# A-14732-40023.net
KiCad netlist of a schematic drawn in EAGLE
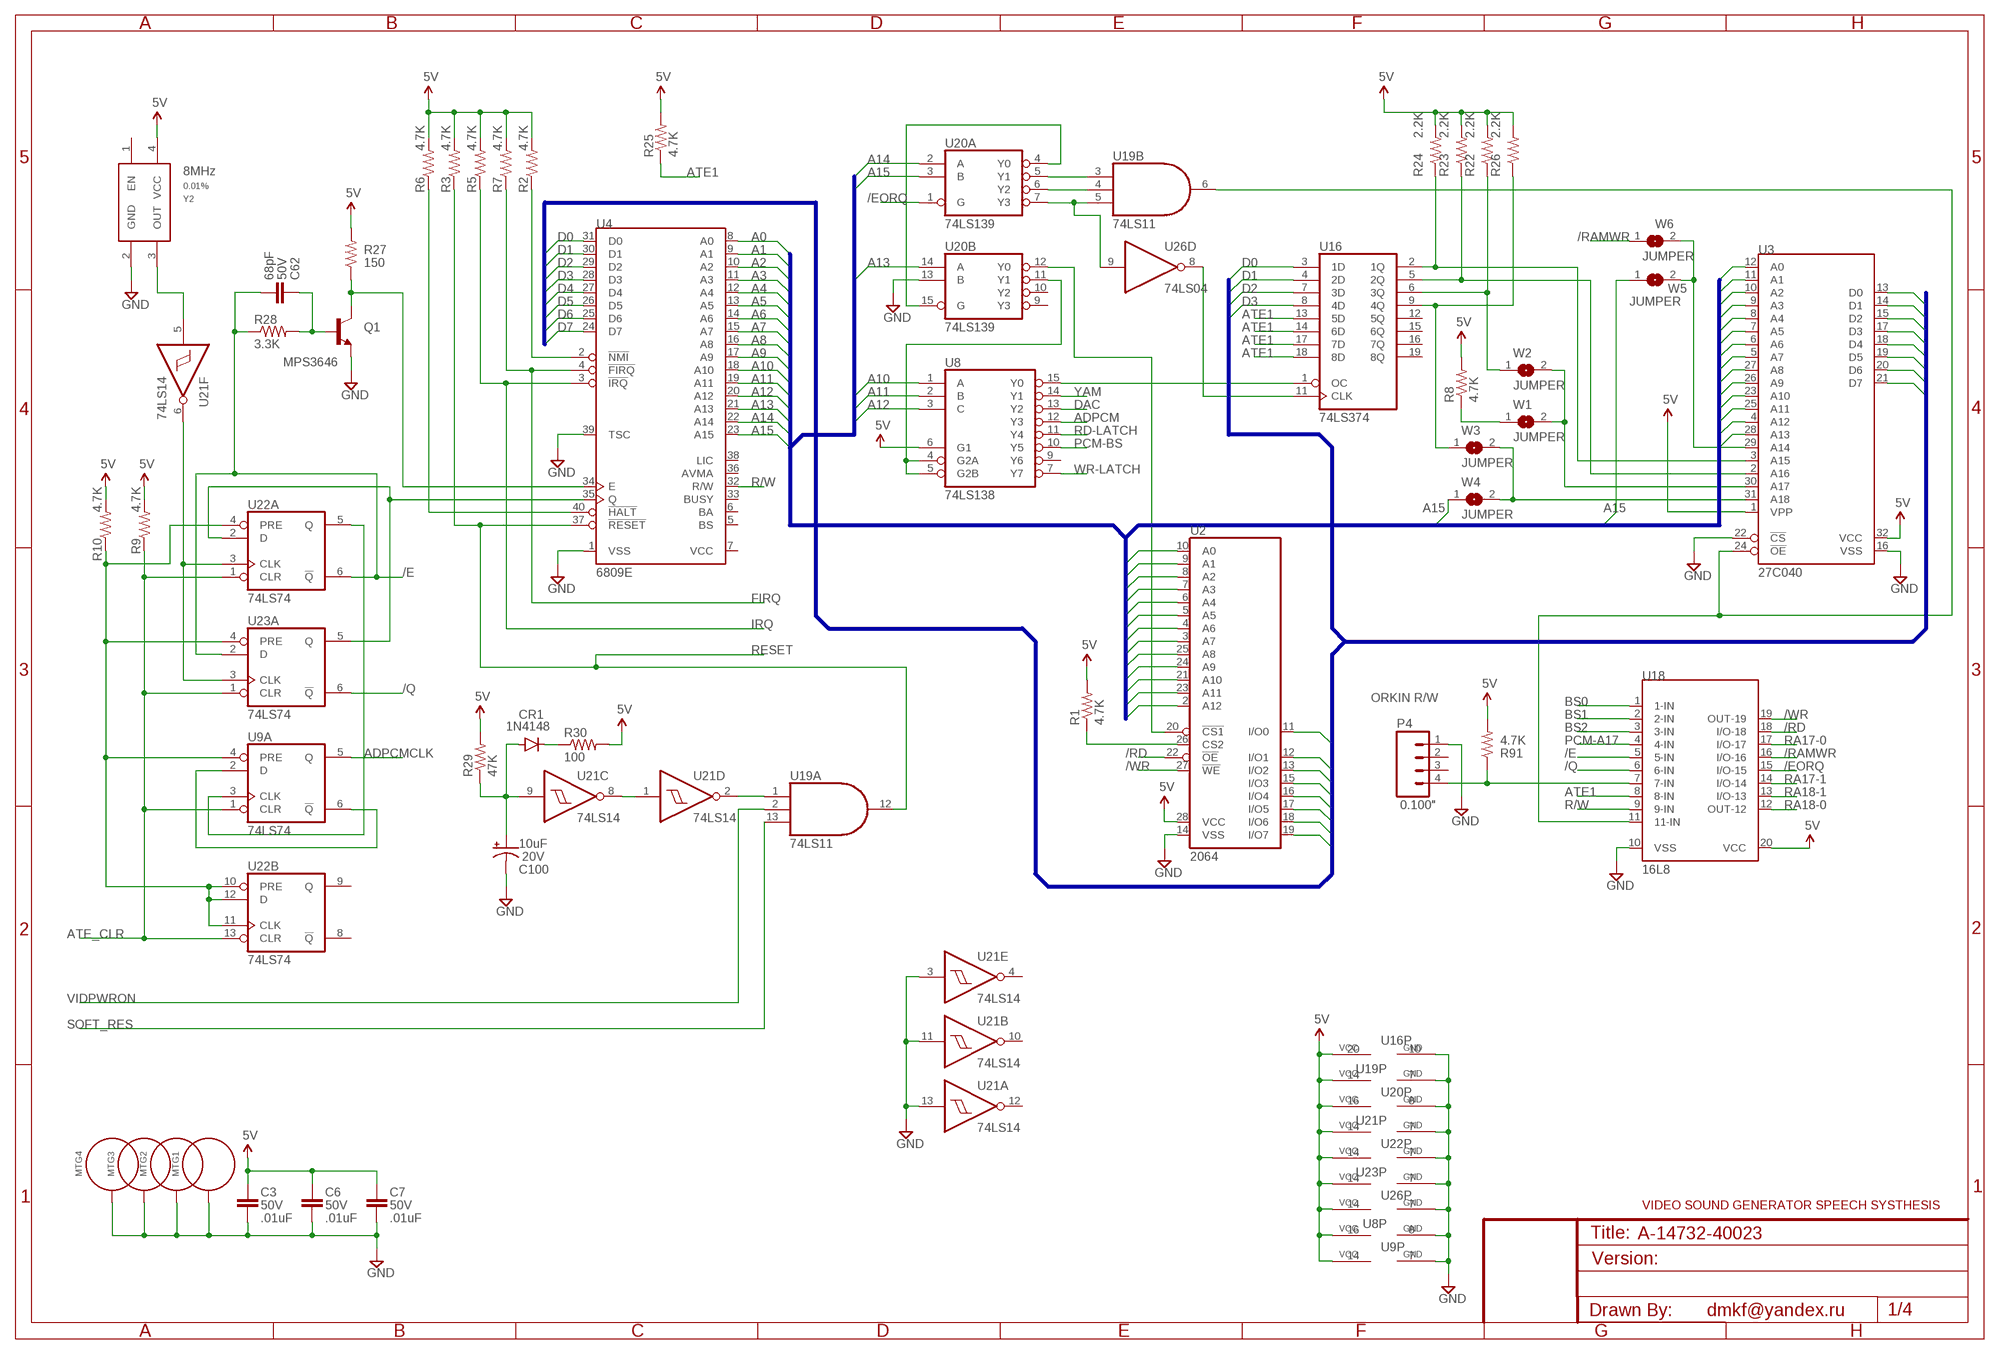
[diagram p0: schematic, sheet 1]
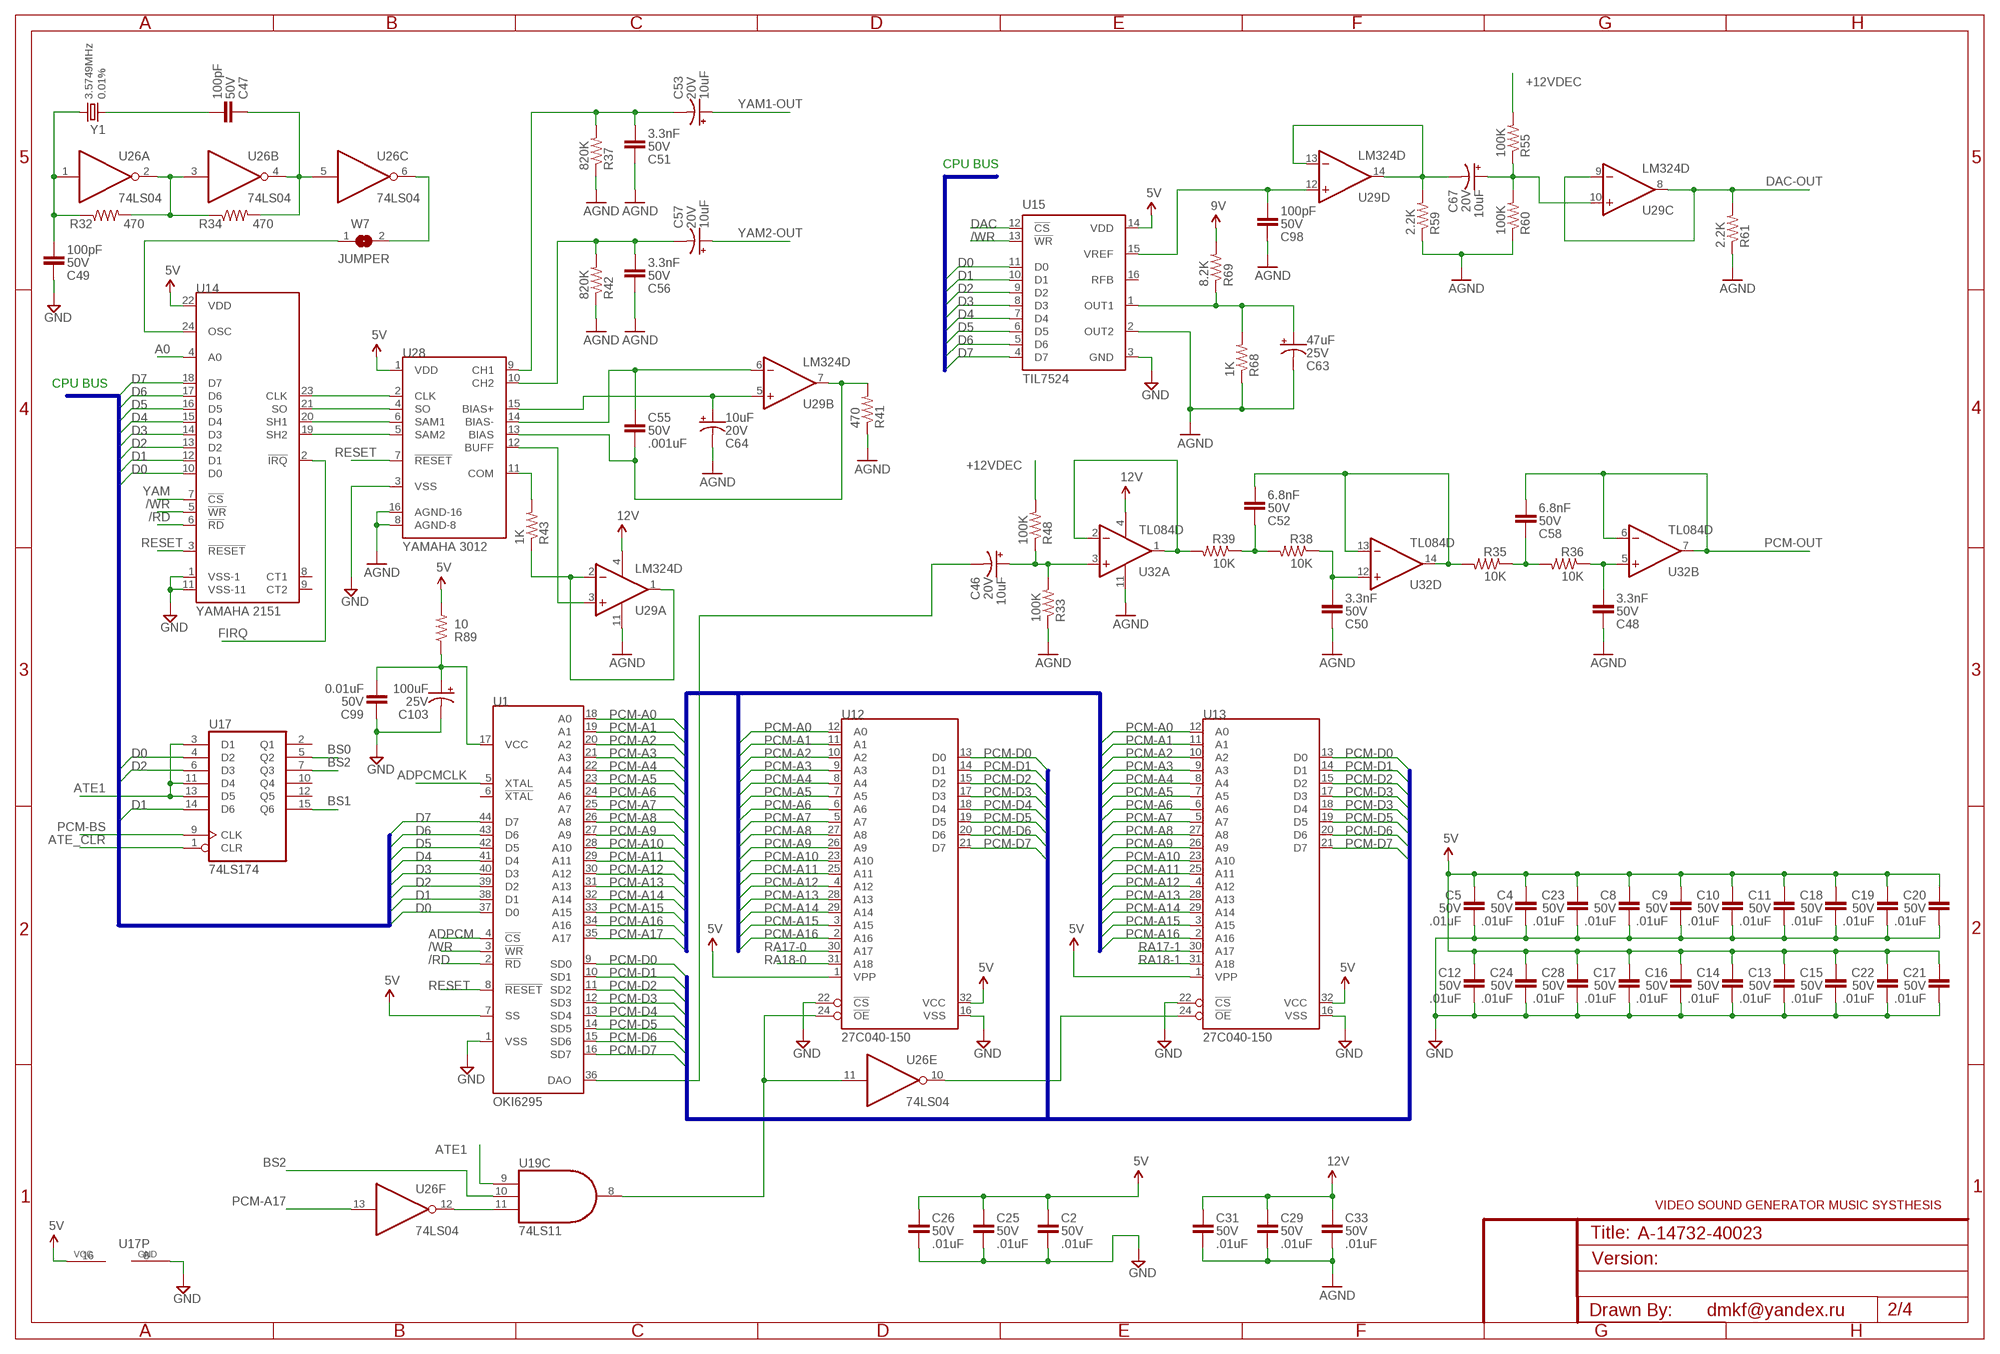
[diagram p1: schematic, sheet 2]
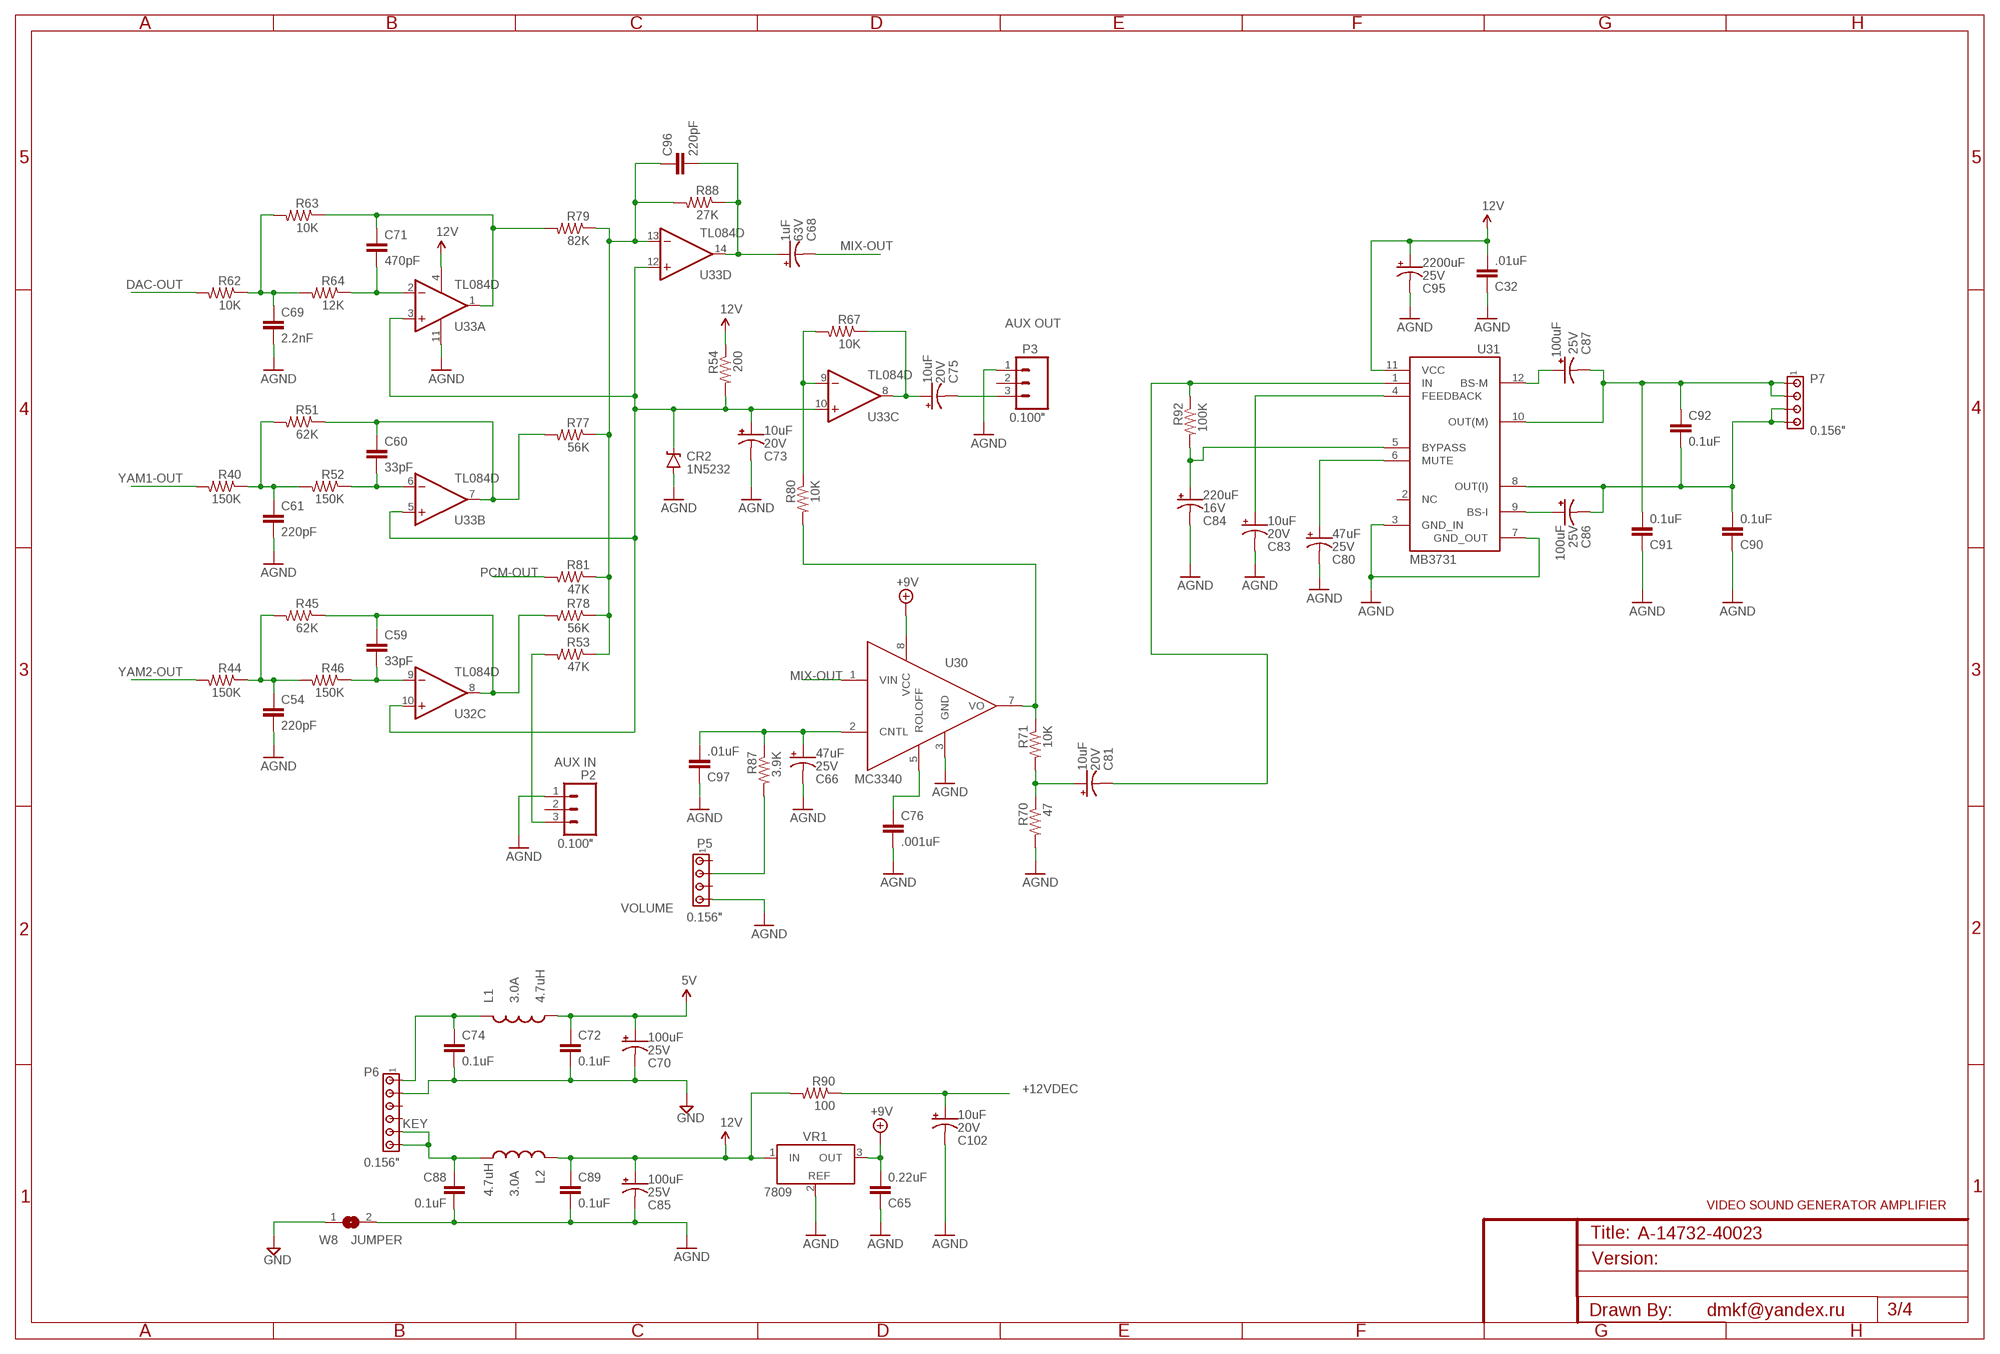
[diagram p2: schematic, sheet 3]
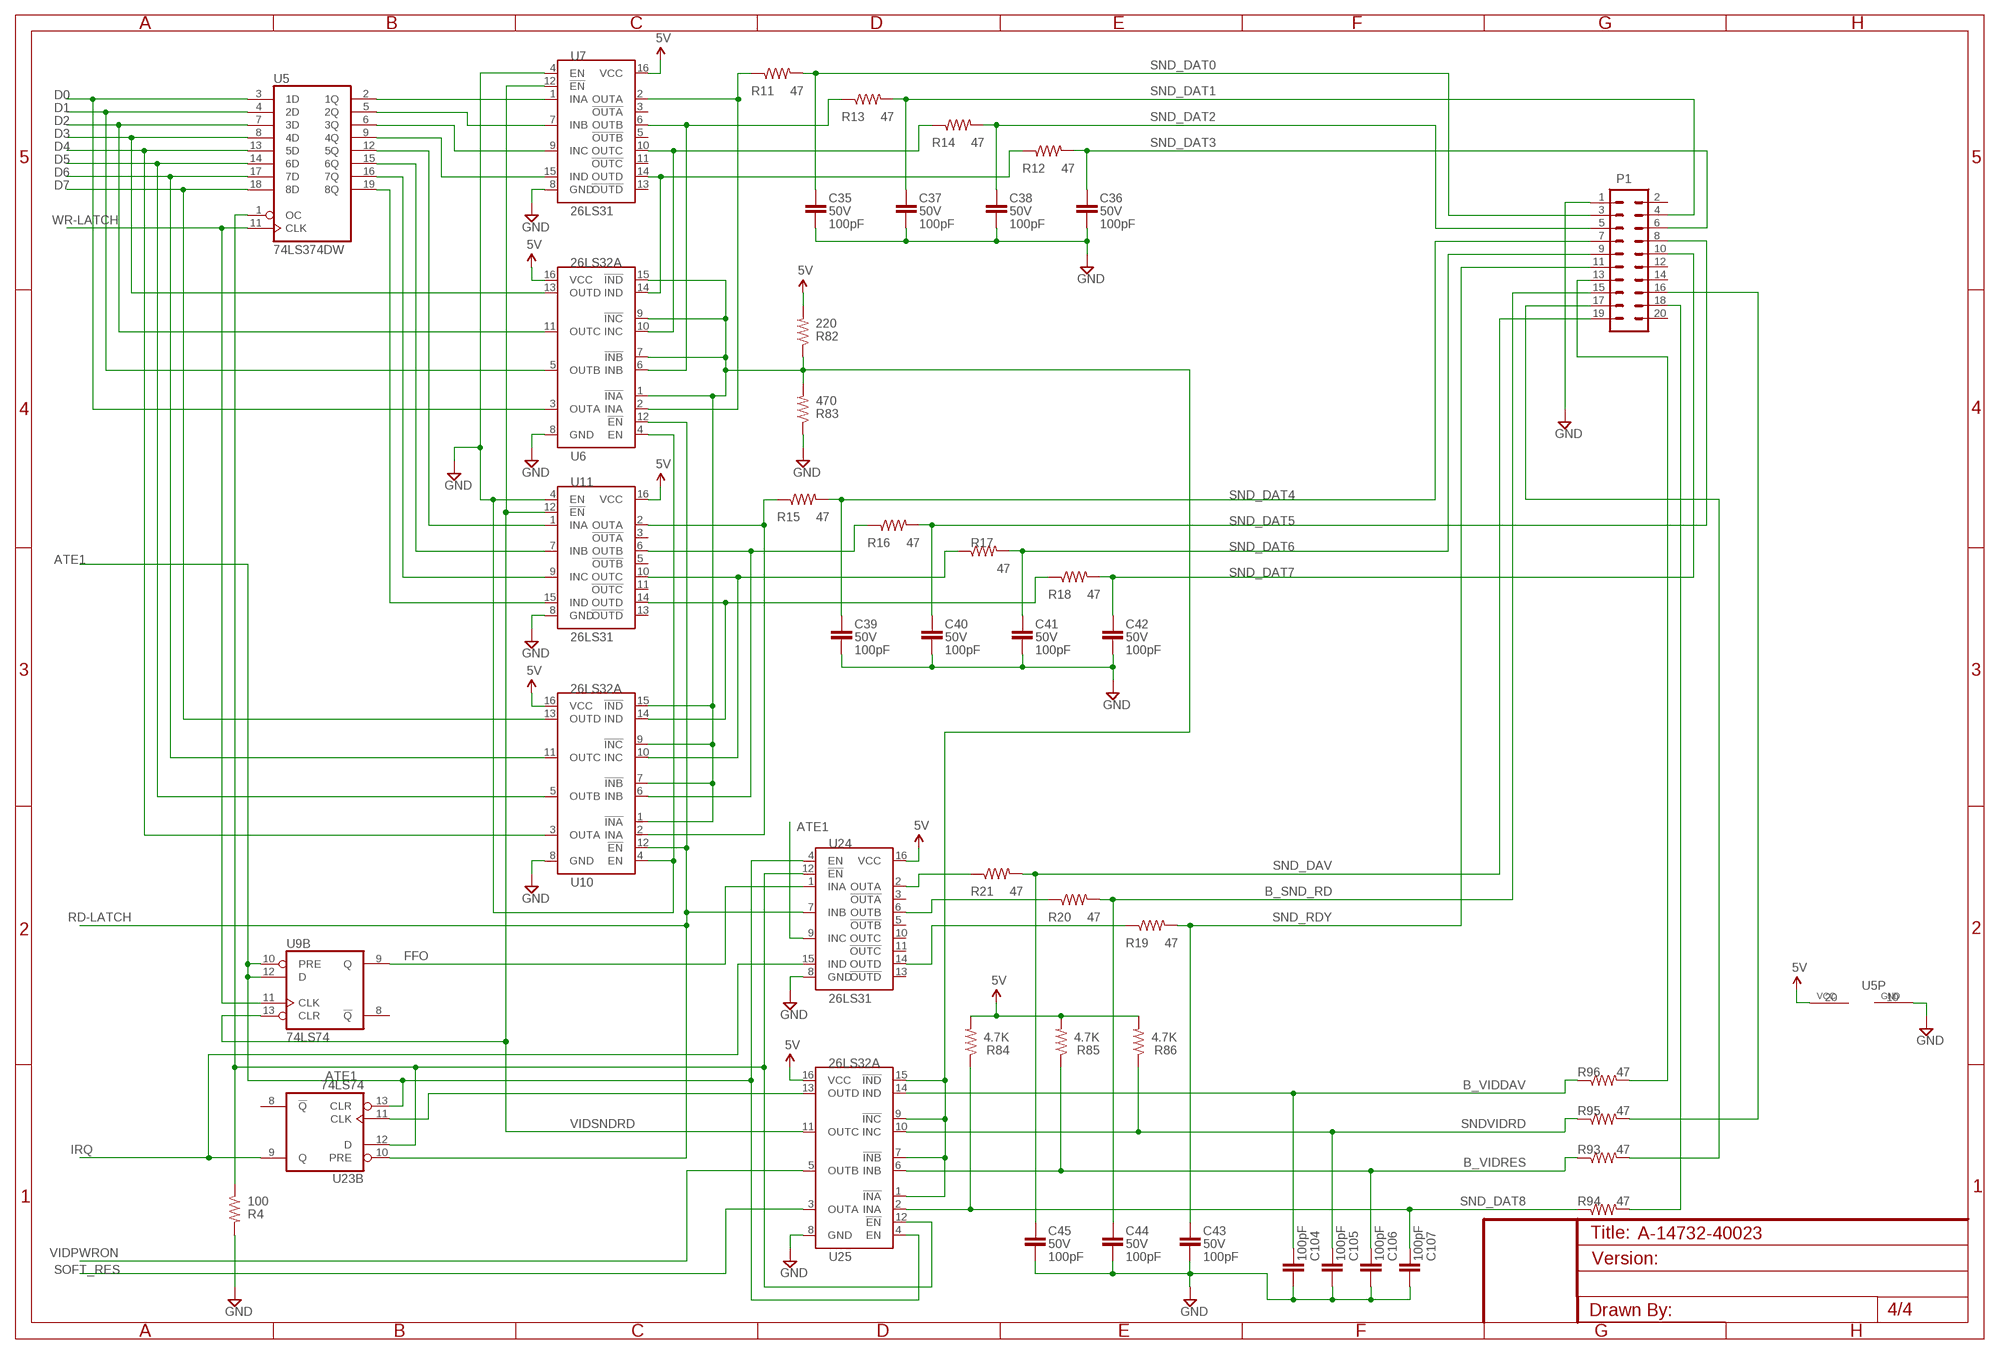
[diagram p3: schematic, sheet 4]

(export (version "E")
  (design (tool "Eeschema 10.0.6"))
  (components
    (comp (ref "C35")
      (value "100pF")
      (footprint "eagle-import:0805")
      (fields (field (name "VOLTAGE") "50V"))
      (libsource (lib "eagle-import") (part "CAP0805"))
    )
    (comp (ref "C36")
      (value "100pF")
      (footprint "eagle-import:0805")
      (fields (field (name "VOLTAGE") "50V"))
      (libsource (lib "eagle-import") (part "CAP0805"))
    )
    (comp (ref "C37")
      (value "100pF")
      (footprint "eagle-import:0805")
      (fields (field (name "VOLTAGE") "50V"))
      (libsource (lib "eagle-import") (part "CAP0805"))
    )
    (comp (ref "C38")
      (value "100pF")
      (footprint "eagle-import:0805")
      (fields (field (name "VOLTAGE") "50V"))
      (libsource (lib "eagle-import") (part "CAP0805"))
    )
    (comp (ref "C39")
      (value "100pF")
      (footprint "eagle-import:0805")
      (fields (field (name "VOLTAGE") "50V"))
      (libsource (lib "eagle-import") (part "CAP0805"))
    )
    (comp (ref "C40")
      (value "100pF")
      (footprint "eagle-import:0805")
      (fields (field (name "VOLTAGE") "50V"))
      (libsource (lib "eagle-import") (part "CAP0805"))
    )
    (comp (ref "C41")
      (value "100pF")
      (footprint "eagle-import:0805")
      (fields (field (name "VOLTAGE") "50V"))
      (libsource (lib "eagle-import") (part "CAP0805"))
    )
    (comp (ref "C42")
      (value "100pF")
      (footprint "eagle-import:0805")
      (fields (field (name "VOLTAGE") "50V"))
      (libsource (lib "eagle-import") (part "CAP0805"))
    )
    (comp (ref "C43")
      (value "100pF")
      (footprint "eagle-import:0805")
      (fields (field (name "VOLTAGE") "50V"))
      (libsource (lib "eagle-import") (part "CAP0805"))
    )
    (comp (ref "C44")
      (value "100pF")
      (footprint "eagle-import:0805")
      (fields (field (name "VOLTAGE") "50V"))
      (libsource (lib "eagle-import") (part "CAP0805"))
    )
    (comp (ref "C45")
      (value "100pF")
      (footprint "eagle-import:0805")
      (fields (field (name "VOLTAGE") "50V"))
      (libsource (lib "eagle-import") (part "CAP0805"))
    )
    (comp (ref "C104")
      (value "100pF")
      (footprint "eagle-import:0805")
      (fields (field (name "VOLTAGE") "50V"))
      (libsource (lib "eagle-import") (part "CAP0805"))
    )
    (comp (ref "C105")
      (value "100pF")
      (footprint "eagle-import:0805")
      (fields (field (name "VOLTAGE") "50V"))
      (libsource (lib "eagle-import") (part "CAP0805"))
    )
    (comp (ref "C106")
      (value "100pF")
      (footprint "eagle-import:0805")
      (fields (field (name "VOLTAGE") "50V"))
      (libsource (lib "eagle-import") (part "CAP0805"))
    )
    (comp (ref "C107")
      (value "100pF")
      (footprint "eagle-import:0805")
      (fields (field (name "VOLTAGE") "50V"))
      (libsource (lib "eagle-import") (part "CAP0805"))
    )
    (comp (ref "P1")
      (value "M10X2ROUND_NOSILK")
      (footprint "eagle-import:2X10_ROUND_NOSILK")
      (libsource (lib "eagle-import") (part "M10X2ROUND_NOSILK"))
    )
    (comp (ref "R4")
      (value "100")
      (footprint "eagle-import:0805")
      (libsource (lib "eagle-import") (part "RESISTOR0805-RES"))
    )
    (comp (ref "R11")
      (value "47")
      (footprint "eagle-import:0805")
      (libsource (lib "eagle-import") (part "RESISTOR0805-RES"))
    )
    (comp (ref "R12")
      (value "47")
      (footprint "eagle-import:0805")
      (libsource (lib "eagle-import") (part "RESISTOR0805-RES"))
    )
    (comp (ref "R13")
      (value "47")
      (footprint "eagle-import:0805")
      (libsource (lib "eagle-import") (part "RESISTOR0805-RES"))
    )
    (comp (ref "R14")
      (value "47")
      (footprint "eagle-import:0805")
      (libsource (lib "eagle-import") (part "RESISTOR0805-RES"))
    )
    (comp (ref "R15")
      (value "47")
      (footprint "eagle-import:R1206")
      (libsource (lib "eagle-import") (part "R-US_R1206"))
    )
    (comp (ref "R16")
      (value "47")
      (footprint "eagle-import:R1206")
      (libsource (lib "eagle-import") (part "R-US_R1206"))
    )
    (comp (ref "R17")
      (value "47")
      (footprint "eagle-import:R1206")
      (libsource (lib "eagle-import") (part "R-US_R1206"))
    )
    (comp (ref "R18")
      (value "47")
      (footprint "eagle-import:R1206")
      (libsource (lib "eagle-import") (part "R-US_R1206"))
    )
    (comp (ref "R19")
      (value "47")
      (footprint "eagle-import:0805")
      (libsource (lib "eagle-import") (part "RESISTOR0805-RES"))
    )
    (comp (ref "R20")
      (value "47")
      (footprint "eagle-import:0805")
      (libsource (lib "eagle-import") (part "RESISTOR0805-RES"))
    )
    (comp (ref "R21")
      (value "47")
      (footprint "eagle-import:0805")
      (libsource (lib "eagle-import") (part "RESISTOR0805-RES"))
    )
    (comp (ref "R82")
      (value "220")
      (footprint "eagle-import:R1206")
      (libsource (lib "eagle-import") (part "R-US_R1206"))
    )
    (comp (ref "R83")
      (value "470")
      (footprint "eagle-import:R1206")
      (libsource (lib "eagle-import") (part "R-US_R1206"))
    )
    (comp (ref "R84")
      (value "4.7K")
      (footprint "eagle-import:0805")
      (libsource (lib "eagle-import") (part "RESISTOR0805-RES"))
    )
    (comp (ref "R85")
      (value "4.7K")
      (footprint "eagle-import:0805")
      (libsource (lib "eagle-import") (part "RESISTOR0805-RES"))
    )
    (comp (ref "R86")
      (value "4.7K")
      (footprint "eagle-import:0805")
      (libsource (lib "eagle-import") (part "RESISTOR0805-RES"))
    )
    (comp (ref "R93")
      (value "47")
      (footprint "eagle-import:0805")
      (libsource (lib "eagle-import") (part "RESISTOR0805-RES"))
    )
    (comp (ref "R94")
      (value "47")
      (footprint "eagle-import:0805")
      (libsource (lib "eagle-import") (part "RESISTOR0805-RES"))
    )
    (comp (ref "R95")
      (value "47")
      (footprint "eagle-import:0805")
      (libsource (lib "eagle-import") (part "RESISTOR0805-RES"))
    )
    (comp (ref "R96")
      (value "47")
      (footprint "eagle-import:0805")
      (libsource (lib "eagle-import") (part "RESISTOR0805-RES"))
    )
    (comp (ref "U5")
      (value "74LS374DW")
      (footprint "eagle-import:SO20W")
      (libsource (lib "eagle-import") (part "74374DWLS"))
    )
    (comp (ref "U6")
      (value "26LS32A")
      (footprint "eagle-import:SO16")
      (libsource (lib "eagle-import") (part "26LS32A"))
    )
    (comp (ref "U7")
      (value "26LS31")
      (footprint "eagle-import:SO16")
      (libsource (lib "eagle-import") (part "26LS31"))
    )
    (comp (ref "U9")
      (value "74LS74")
      (footprint "eagle-import:SO14")
      (libsource (lib "eagle-import") (part "7474DLS"))
    )
    (comp (ref "U10")
      (value "26LS32A")
      (footprint "eagle-import:SO16")
      (libsource (lib "eagle-import") (part "26LS32A"))
    )
    (comp (ref "U11")
      (value "26LS31")
      (footprint "eagle-import:SO16")
      (libsource (lib "eagle-import") (part "26LS31"))
    )
    (comp (ref "U23")
      (value "74LS74")
      (footprint "eagle-import:SO14")
      (libsource (lib "eagle-import") (part "7474DLS"))
    )
    (comp (ref "U24")
      (value "26LS31")
      (footprint "eagle-import:SO16")
      (libsource (lib "eagle-import") (part "26LS31"))
    )
    (comp (ref "U25")
      (value "26LS32A")
      (footprint "eagle-import:SO16")
      (libsource (lib "eagle-import") (part "26LS32A"))
    )
    (comp (ref "C32")
      (value ".01uF")
      (footprint "eagle-import:0805")
      (fields (field (name "VOLTAGE") "50V"))
      (libsource (lib "eagle-import") (part "CAP0805"))
    )
    (comp (ref "C54")
      (value "220pF")
      (footprint "eagle-import:0805")
      (fields (field (name "VOLTAGE") "50V"))
      (libsource (lib "eagle-import") (part "CAP0805"))
    )
    (comp (ref "C59")
      (value "33pF")
      (footprint "eagle-import:0805")
      (fields (field (name "VOLTAGE") "50V"))
      (libsource (lib "eagle-import") (part "CAP0805"))
    )
    (comp (ref "C60")
      (value "33pF")
      (footprint "eagle-import:0805")
      (fields (field (name "VOLTAGE") "50V"))
      (libsource (lib "eagle-import") (part "CAP0805"))
    )
    (comp (ref "C61")
      (value "220pF")
      (footprint "eagle-import:0805")
      (fields (field (name "VOLTAGE") "50V"))
      (libsource (lib "eagle-import") (part "CAP0805"))
    )
    (comp (ref "C65")
      (value "0.22uF")
      (footprint "eagle-import:0805")
      (fields (field (name "VOLTAGE") "50V"))
      (libsource (lib "eagle-import") (part "CAP0805"))
    )
    (comp (ref "C66")
      (value "47uF")
      (footprint "eagle-import:PANASONIC_D")
      (fields (field (name "VOLTAGE") "25V"))
      (libsource (lib "eagle-import") (part "CAP_POLD"))
    )
    (comp (ref "C68")
      (value "1uF")
      (footprint "eagle-import:PANASONIC_C")
      (fields (field (name "VOLTAGE") "63V"))
      (libsource (lib "eagle-import") (part "CAP_POLC"))
    )
    (comp (ref "C69")
      (value "2.2nF")
      (footprint "eagle-import:0805")
      (fields (field (name "VOLTAGE") "50V"))
      (libsource (lib "eagle-import") (part "CAP0805"))
    )
    (comp (ref "C70")
      (value "100uF")
      (footprint "eagle-import:PANASONIC_D")
      (fields (field (name "VOLTAGE") "25V"))
      (libsource (lib "eagle-import") (part "CAP_POLD"))
    )
    (comp (ref "C71")
      (value "470pF")
      (footprint "eagle-import:0805")
      (fields (field (name "VOLTAGE") "50V"))
      (libsource (lib "eagle-import") (part "CAP0805"))
    )
    (comp (ref "C72")
      (value "0.1uF")
      (footprint "eagle-import:0805")
      (fields (field (name "VOLTAGE") "50V"))
      (libsource (lib "eagle-import") (part "CAP0805"))
    )
    (comp (ref "C73")
      (value "10uF")
      (footprint "eagle-import:PANASONIC_C")
      (fields (field (name "VOLTAGE") "20V"))
      (libsource (lib "eagle-import") (part "CAP_POLC"))
    )
    (comp (ref "C74")
      (value "0.1uF")
      (footprint "eagle-import:0805")
      (fields (field (name "VOLTAGE") "50V"))
      (libsource (lib "eagle-import") (part "CAP0805"))
    )
    (comp (ref "C75")
      (value "10uF")
      (footprint "eagle-import:PANASONIC_C")
      (fields (field (name "VOLTAGE") "20V"))
      (libsource (lib "eagle-import") (part "CAP_POLC"))
    )
    (comp (ref "C76")
      (value ".001uF")
      (footprint "eagle-import:0805")
      (fields (field (name "VOLTAGE") "50V"))
      (libsource (lib "eagle-import") (part "CAP0805"))
    )
    (comp (ref "C80")
      (value "47uF")
      (footprint "eagle-import:PANASONIC_D")
      (fields (field (name "VOLTAGE") "25V"))
      (libsource (lib "eagle-import") (part "CAP_POLD"))
    )
    (comp (ref "C81")
      (value "10uF")
      (footprint "eagle-import:PANASONIC_C")
      (fields (field (name "VOLTAGE") "20V"))
      (libsource (lib "eagle-import") (part "CAP_POLC"))
    )
    (comp (ref "C83")
      (value "10uF")
      (footprint "eagle-import:PANASONIC_C")
      (fields (field (name "VOLTAGE") "20V"))
      (libsource (lib "eagle-import") (part "CAP_POLC"))
    )
    (comp (ref "C84")
      (value "220uF")
      (footprint "eagle-import:PANASONIC_E")
      (fields (field (name "VOLTAGE") "16V"))
      (libsource (lib "eagle-import") (part "CAP_POLE"))
    )
    (comp (ref "C85")
      (value "100uF")
      (footprint "eagle-import:PANASONIC_D")
      (fields (field (name "VOLTAGE") "25V"))
      (libsource (lib "eagle-import") (part "CAP_POLD"))
    )
    (comp (ref "C86")
      (value "100uF")
      (footprint "eagle-import:PANASONIC_D")
      (fields (field (name "VOLTAGE") "25V"))
      (libsource (lib "eagle-import") (part "CAP_POLD"))
    )
    (comp (ref "C87")
      (value "100uF")
      (footprint "eagle-import:PANASONIC_D")
      (fields (field (name "VOLTAGE") "25V"))
      (libsource (lib "eagle-import") (part "CAP_POLD"))
    )
    (comp (ref "C88")
      (value "0.1uF")
      (footprint "eagle-import:0805")
      (fields (field (name "VOLTAGE") "50V"))
      (libsource (lib "eagle-import") (part "CAP0805"))
    )
    (comp (ref "C89")
      (value "0.1uF")
      (footprint "eagle-import:0805")
      (fields (field (name "VOLTAGE") "50V"))
      (libsource (lib "eagle-import") (part "CAP0805"))
    )
    (comp (ref "C90")
      (value "0.1uF")
      (footprint "eagle-import:0805")
      (fields (field (name "VOLTAGE") "50V"))
      (libsource (lib "eagle-import") (part "CAP0805"))
    )
    (comp (ref "C91")
      (value "0.1uF")
      (footprint "eagle-import:0805")
      (fields (field (name "VOLTAGE") "50V"))
      (libsource (lib "eagle-import") (part "CAP0805"))
    )
    (comp (ref "C92")
      (value "0.1uF")
      (footprint "eagle-import:0805")
      (fields (field (name "VOLTAGE") "50V"))
      (libsource (lib "eagle-import") (part "CAP0805"))
    )
    (comp (ref "C95")
      (value "2200uF")
      (footprint "eagle-import:CPOL-RADIAL-1000UF-63V")
      (fields (field (name "VOLTAGE") "25V"))
      (libsource (lib "eagle-import") (part "CAP_POLPTH3"))
    )
    (comp (ref "C96")
      (value "220pF")
      (footprint "eagle-import:0805")
      (fields (field (name "VOLTAGE") "50V"))
      (libsource (lib "eagle-import") (part "CAP0805"))
    )
    (comp (ref "C97")
      (value ".01uF")
      (footprint "eagle-import:0805")
      (fields (field (name "VOLTAGE") "50V"))
      (libsource (lib "eagle-import") (part "CAP0805"))
    )
    (comp (ref "C102")
      (value "10uF")
      (footprint "eagle-import:PANASONIC_C")
      (fields (field (name "VOLTAGE") "20V"))
      (libsource (lib "eagle-import") (part "CAP_POLC"))
    )
    (comp (ref "CR2")
      (value "1N5232")
      (footprint "eagle-import:SOT23")
      (libsource (lib "eagle-import") (part "1N5232"))
    )
    (comp (ref "L1")
      (value "4.7uH")
      (footprint "eagle-import:NPI75C")
      (fields (field (name "CUR") "3.0A"))
      (libsource (lib "eagle-import") (part "INDUCTORNPI75"))
    )
    (comp (ref "L2")
      (value "4.7uH")
      (footprint "eagle-import:NPI75C")
      (fields (field (name "CURRENT") "3.0A"))
      (libsource (lib "eagle-import") (part "INDUCTORNPI75"))
    )
    (comp (ref "P2")
      (value "AUX IN")
      (footprint "eagle-import:1X03_LONGPADS")
      (fields (field (name "PITCH") "0.100\""))
      (libsource (lib "eagle-import") (part "M03LONGPADS"))
    )
    (comp (ref "P3")
      (value "AUX OUT")
      (footprint "eagle-import:1X03_LONGPADS")
      (fields (field (name "PITCH") "0.100\""))
      (libsource (lib "eagle-import") (part "M03LONGPADS"))
    )
    (comp (ref "P5")
      (value "VOLUME")
      (footprint "eagle-import:1X4MTA")
      (fields (field (name "SIZE") "0.156\""))
      (libsource (lib "eagle-import") (part "MTA04-156"))
    )
    (comp (ref "P6")
      (value "0.156\"")
      (footprint "eagle-import:1X6MTA")
      (libsource (lib "eagle-import") (part "MTA06-156"))
    )
    (comp (ref "P7")
      (value "0.156\"")
      (footprint "eagle-import:1X4MTA")
      (libsource (lib "eagle-import") (part "MTA04-156"))
    )
    (comp (ref "R40")
      (value "150K")
      (footprint "eagle-import:0805")
      (libsource (lib "eagle-import") (part "RESISTOR0805-RES"))
    )
    (comp (ref "R44")
      (value "150K")
      (footprint "eagle-import:0805")
      (libsource (lib "eagle-import") (part "RESISTOR0805-RES"))
    )
    (comp (ref "R45")
      (value "62K")
      (footprint "eagle-import:0805")
      (libsource (lib "eagle-import") (part "RESISTOR0805-RES"))
    )
    (comp (ref "R46")
      (value "150K")
      (footprint "eagle-import:0805")
      (libsource (lib "eagle-import") (part "RESISTOR0805-RES"))
    )
    (comp (ref "R51")
      (value "62K")
      (footprint "eagle-import:0805")
      (libsource (lib "eagle-import") (part "RESISTOR0805-RES"))
    )
    (comp (ref "R52")
      (value "150K")
      (footprint "eagle-import:0805")
      (libsource (lib "eagle-import") (part "RESISTOR0805-RES"))
    )
    (comp (ref "R53")
      (value "47K")
      (footprint "eagle-import:0805")
      (libsource (lib "eagle-import") (part "RESISTOR0805-RES"))
    )
    (comp (ref "R54")
      (value "200")
      (footprint "eagle-import:R1206")
      (libsource (lib "eagle-import") (part "R-US_R1206"))
    )
    (comp (ref "R62")
      (value "10K")
      (footprint "eagle-import:0805")
      (libsource (lib "eagle-import") (part "RESISTOR0805-RES"))
    )
    (comp (ref "R63")
      (value "10K")
      (footprint "eagle-import:0805")
      (libsource (lib "eagle-import") (part "RESISTOR0805-RES"))
    )
    (comp (ref "R64")
      (value "12K")
      (footprint "eagle-import:0805")
      (libsource (lib "eagle-import") (part "RESISTOR0805-RES"))
    )
    (comp (ref "R67")
      (value "10K")
      (footprint "eagle-import:0805")
      (libsource (lib "eagle-import") (part "RESISTOR0805-RES"))
    )
    (comp (ref "R70")
      (value "47")
      (footprint "eagle-import:R1206")
      (libsource (lib "eagle-import") (part "R-US_R1206"))
    )
    (comp (ref "R71")
      (value "10K")
      (footprint "eagle-import:0805")
      (libsource (lib "eagle-import") (part "RESISTOR0805-RES"))
    )
    (comp (ref "R77")
      (value "56K")
      (footprint "eagle-import:0805")
      (libsource (lib "eagle-import") (part "RESISTOR0805-RES"))
    )
    (comp (ref "R78")
      (value "56K")
      (footprint "eagle-import:0805")
      (libsource (lib "eagle-import") (part "RESISTOR0805-RES"))
    )
    (comp (ref "R79")
      (value "82K")
      (footprint "eagle-import:0805")
      (libsource (lib "eagle-import") (part "RESISTOR0805-RES"))
    )
    (comp (ref "R80")
      (value "10K")
      (footprint "eagle-import:0805")
      (libsource (lib "eagle-import") (part "RESISTOR0805-RES"))
    )
    (comp (ref "R81")
      (value "47K")
      (footprint "eagle-import:0805")
      (libsource (lib "eagle-import") (part "RESISTOR0805-RES"))
    )
    (comp (ref "R87")
      (value "3.9K")
      (footprint "eagle-import:0805")
      (libsource (lib "eagle-import") (part "RESISTOR0805-RES"))
    )
    (comp (ref "R88")
      (value "27K")
      (footprint "eagle-import:0805")
      (libsource (lib "eagle-import") (part "RESISTOR0805-RES"))
    )
    (comp (ref "R90")
      (value "100")
      (footprint "eagle-import:R1206")
      (libsource (lib "eagle-import") (part "R-US_R1206"))
    )
    (comp (ref "R92")
      (value "100K")
      (footprint "eagle-import:0805")
      (libsource (lib "eagle-import") (part "RESISTOR0805-RES"))
    )
    (comp (ref "U30")
      (value "MC3340")
      (footprint "eagle-import:MC3340")
      (libsource (lib "eagle-import") (part "MC3340"))
    )
    (comp (ref "U31")
      (value "MB3731")
      (footprint "eagle-import:SIP12")
      (libsource (lib "eagle-import") (part "MB3731"))
    )
    (comp (ref "U32")
      (value "TL084D")
      (footprint "eagle-import:SO14")
      (libsource (lib "eagle-import") (part "TL084D"))
    )
    (comp (ref "U33")
      (value "TL084D")
      (footprint "eagle-import:SO14")
      (libsource (lib "eagle-import") (part "TL084D"))
    )
    (comp (ref "VR1")
      (value "7809")
      (footprint "eagle-import:7809-D2PAK")
      (fields (field (name "PARTNUMBER") "5460-12743-00"))
      (libsource (lib "eagle-import") (part "7809D2PAK"))
    )
    (comp (ref "W8")
      (value "JUMPER")
      (footprint "eagle-import:SJ")
      (libsource (lib "eagle-import") (part "SJ"))
    )
    (comp (ref "C2")
      (value ".01uF")
      (footprint "eagle-import:0805")
      (fields (field (name "VOLTAGE") "50V"))
      (libsource (lib "eagle-import") (part "CAP0805"))
    )
    (comp (ref "C4")
      (value ".01uF")
      (footprint "eagle-import:0805")
      (fields (field (name "VOLTAGE") "50V"))
      (libsource (lib "eagle-import") (part "CAP0805"))
    )
    (comp (ref "C5")
      (value ".01uF")
      (footprint "eagle-import:0805")
      (fields (field (name "VOLTAGE") "50V"))
      (libsource (lib "eagle-import") (part "CAP0805"))
    )
    (comp (ref "C8")
      (value ".01uF")
      (footprint "eagle-import:0805")
      (fields (field (name "VOLTAGE") "50V"))
      (libsource (lib "eagle-import") (part "CAP0805"))
    )
    (comp (ref "C9")
      (value ".01uF")
      (footprint "eagle-import:0805")
      (fields (field (name "VOLTAGE") "50V"))
      (libsource (lib "eagle-import") (part "CAP0805"))
    )
    (comp (ref "C10")
      (value ".01uF")
      (footprint "eagle-import:0805")
      (fields (field (name "VOLTAGE") "50V"))
      (libsource (lib "eagle-import") (part "CAP0805"))
    )
    (comp (ref "C11")
      (value ".01uF")
      (footprint "eagle-import:0805")
      (fields (field (name "VOLTAGE") "50V"))
      (libsource (lib "eagle-import") (part "CAP0805"))
    )
    (comp (ref "C12")
      (value ".01uF")
      (footprint "eagle-import:0805")
      (fields (field (name "VOLTAGE") "50V"))
      (libsource (lib "eagle-import") (part "CAP0805"))
    )
    (comp (ref "C13")
      (value ".01uF")
      (footprint "eagle-import:0805")
      (fields (field (name "VOLTAGE") "50V"))
      (libsource (lib "eagle-import") (part "CAP0805"))
    )
    (comp (ref "C14")
      (value ".01uF")
      (footprint "eagle-import:0805")
      (fields (field (name "VOLTAGE") "50V"))
      (libsource (lib "eagle-import") (part "CAP0805"))
    )
    (comp (ref "C15")
      (value ".01uF")
      (footprint "eagle-import:0805")
      (fields (field (name "VOLTAGE") "50V"))
      (libsource (lib "eagle-import") (part "CAP0805"))
    )
    (comp (ref "C16")
      (value ".01uF")
      (footprint "eagle-import:0805")
      (fields (field (name "VOLTAGE") "50V"))
      (libsource (lib "eagle-import") (part "CAP0805"))
    )
    (comp (ref "C17")
      (value ".01uF")
      (footprint "eagle-import:0805")
      (fields (field (name "VOLTAGE") "50V"))
      (libsource (lib "eagle-import") (part "CAP0805"))
    )
    (comp (ref "C18")
      (value ".01uF")
      (footprint "eagle-import:0805")
      (fields (field (name "VOLTAGE") "50V"))
      (libsource (lib "eagle-import") (part "CAP0805"))
    )
    (comp (ref "C19")
      (value ".01uF")
      (footprint "eagle-import:0805")
      (fields (field (name "VOLTAGE") "50V"))
      (libsource (lib "eagle-import") (part "CAP0805"))
    )
    (comp (ref "C20")
      (value ".01uF")
      (footprint "eagle-import:0805")
      (fields (field (name "VOLTAGE") "50V"))
      (libsource (lib "eagle-import") (part "CAP0805"))
    )
    (comp (ref "C21")
      (value ".01uF")
      (footprint "eagle-import:0805")
      (fields (field (name "VOLTAGE") "50V"))
      (libsource (lib "eagle-import") (part "CAP0805"))
    )
    (comp (ref "C22")
      (value ".01uF")
      (footprint "eagle-import:0805")
      (fields (field (name "VOLTAGE") "50V"))
      (libsource (lib "eagle-import") (part "CAP0805"))
    )
    (comp (ref "C23")
      (value ".01uF")
      (footprint "eagle-import:0805")
      (fields (field (name "VOLTAGE") "50V"))
      (libsource (lib "eagle-import") (part "CAP0805"))
    )
    (comp (ref "C24")
      (value ".01uF")
      (footprint "eagle-import:0805")
      (fields (field (name "VOLTAGE") "50V"))
      (libsource (lib "eagle-import") (part "CAP0805"))
    )
    (comp (ref "C25")
      (value ".01uF")
      (footprint "eagle-import:0805")
      (fields (field (name "VOLTAGE") "50V"))
      (libsource (lib "eagle-import") (part "CAP0805"))
    )
    (comp (ref "C26")
      (value ".01uF")
      (footprint "eagle-import:0805")
      (fields (field (name "VOLTAGE") "50V"))
      (libsource (lib "eagle-import") (part "CAP0805"))
    )
    (comp (ref "C28")
      (value ".01uF")
      (footprint "eagle-import:0805")
      (fields (field (name "VOLTAGE") "50V"))
      (libsource (lib "eagle-import") (part "CAP0805"))
    )
    (comp (ref "C29")
      (value ".01uF")
      (footprint "eagle-import:0805")
      (fields (field (name "VOLTAGE") "50V"))
      (libsource (lib "eagle-import") (part "CAP0805"))
    )
    (comp (ref "C31")
      (value ".01uF")
      (footprint "eagle-import:0805")
      (fields (field (name "VOLTAGE") "50V"))
      (libsource (lib "eagle-import") (part "CAP0805"))
    )
    (comp (ref "C33")
      (value ".01uF")
      (footprint "eagle-import:0805")
      (fields (field (name "VOLTAGE") "50V"))
      (libsource (lib "eagle-import") (part "CAP0805"))
    )
    (comp (ref "C46")
      (value "10uF")
      (footprint "eagle-import:PANASONIC_C")
      (fields (field (name "VOLTAGE") "20V"))
      (libsource (lib "eagle-import") (part "CAP_POLC"))
    )
    (comp (ref "C47")
      (value "100pF")
      (footprint "eagle-import:0805")
      (fields (field (name "VOLTAGE") "50V"))
      (libsource (lib "eagle-import") (part "CAP0805"))
    )
    (comp (ref "C48")
      (value "3.3nF")
      (footprint "eagle-import:0805")
      (fields (field (name "VOLTAGE") "50V"))
      (libsource (lib "eagle-import") (part "CAP0805"))
    )
    (comp (ref "C49")
      (value "100pF")
      (footprint "eagle-import:0805")
      (fields (field (name "VOLTAGE") "50V"))
      (libsource (lib "eagle-import") (part "CAP0805"))
    )
    (comp (ref "C50")
      (value "3.3nF")
      (footprint "eagle-import:0805")
      (fields (field (name "VOLTAGE") "50V"))
      (libsource (lib "eagle-import") (part "CAP0805"))
    )
    (comp (ref "C51")
      (value "3.3nF")
      (footprint "eagle-import:0805")
      (fields (field (name "VOLTAGE") "50V"))
      (libsource (lib "eagle-import") (part "CAP0805"))
    )
    (comp (ref "C52")
      (value "6.8nF")
      (footprint "eagle-import:0805")
      (fields (field (name "VOLTAGE") "50V"))
      (libsource (lib "eagle-import") (part "CAP0805"))
    )
    (comp (ref "C53")
      (value "10uF")
      (footprint "eagle-import:PANASONIC_C")
      (fields (field (name "VOLTAGE") "20V"))
      (libsource (lib "eagle-import") (part "CAP_POLC"))
    )
    (comp (ref "C55")
      (value ".001uF")
      (footprint "eagle-import:0805")
      (fields (field (name "VOLTAGE") "50V"))
      (libsource (lib "eagle-import") (part "CAP0805"))
    )
    (comp (ref "C56")
      (value "3.3nF")
      (footprint "eagle-import:0805")
      (fields (field (name "VOLTAGE") "50V"))
      (libsource (lib "eagle-import") (part "CAP0805"))
    )
    (comp (ref "C57")
      (value "10uF")
      (footprint "eagle-import:PANASONIC_C")
      (fields (field (name "VOLTAGE") "20V"))
      (libsource (lib "eagle-import") (part "CAP_POLC"))
    )
    (comp (ref "C58")
      (value "6.8nF")
      (footprint "eagle-import:0805")
      (fields (field (name "VOLTAGE") "50V"))
      (libsource (lib "eagle-import") (part "CAP0805"))
    )
    (comp (ref "C63")
      (value "47uF")
      (footprint "eagle-import:PANASONIC_D")
      (fields (field (name "VOLTAGE") "25V"))
      (libsource (lib "eagle-import") (part "CAP_POLD"))
    )
    (comp (ref "C64")
      (value "10uF")
      (footprint "eagle-import:PANASONIC_C")
      (fields (field (name "VOLTAGE") "20V"))
      (libsource (lib "eagle-import") (part "CAP_POLC"))
    )
    (comp (ref "C67")
      (value "10uF")
      (footprint "eagle-import:PANASONIC_C")
      (fields (field (name "VOLTAGE") "20V"))
      (libsource (lib "eagle-import") (part "CAP_POLC"))
    )
    (comp (ref "C98")
      (value "100pF")
      (footprint "eagle-import:0805")
      (fields (field (name "VOLTAGE") "50V"))
      (libsource (lib "eagle-import") (part "CAP0805"))
    )
    (comp (ref "C99")
      (value "0.01uF")
      (footprint "eagle-import:0805")
      (fields (field (name "VOLTAGE") "50V"))
      (libsource (lib "eagle-import") (part "CAP0805"))
    )
    (comp (ref "C103")
      (value "100uF")
      (footprint "eagle-import:PANASONIC_D")
      (fields (field (name "VOLTAGE") "25V"))
      (libsource (lib "eagle-import") (part "CAP_POLD"))
    )
    (comp (ref "R32")
      (value "470")
      (footprint "eagle-import:0805")
      (libsource (lib "eagle-import") (part "RESISTOR0805-RES"))
    )
    (comp (ref "R33")
      (value "100K")
      (footprint "eagle-import:0805")
      (libsource (lib "eagle-import") (part "RESISTOR0805-RES"))
    )
    (comp (ref "R34")
      (value "470")
      (footprint "eagle-import:0805")
      (libsource (lib "eagle-import") (part "RESISTOR0805-RES"))
    )
    (comp (ref "R35")
      (value "10K")
      (footprint "eagle-import:0805")
      (libsource (lib "eagle-import") (part "RESISTOR0805-RES"))
    )
    (comp (ref "R36")
      (value "10K")
      (footprint "eagle-import:0805")
      (libsource (lib "eagle-import") (part "RESISTOR0805-RES"))
    )
    (comp (ref "R37")
      (value "820K")
      (footprint "eagle-import:0805")
      (libsource (lib "eagle-import") (part "RESISTOR0805-RES"))
    )
    (comp (ref "R38")
      (value "10K")
      (footprint "eagle-import:0805")
      (libsource (lib "eagle-import") (part "RESISTOR0805-RES"))
    )
    (comp (ref "R39")
      (value "10K")
      (footprint "eagle-import:0805")
      (libsource (lib "eagle-import") (part "RESISTOR0805-RES"))
    )
    (comp (ref "R41")
      (value "470")
      (footprint "eagle-import:0805")
      (libsource (lib "eagle-import") (part "RESISTOR0805-RES"))
    )
    (comp (ref "R42")
      (value "820K")
      (footprint "eagle-import:0805")
      (libsource (lib "eagle-import") (part "RESISTOR0805-RES"))
    )
    (comp (ref "R43")
      (value "1K")
      (footprint "eagle-import:0805")
      (libsource (lib "eagle-import") (part "RESISTOR0805-RES"))
    )
    (comp (ref "R48")
      (value "100K")
      (footprint "eagle-import:0805")
      (libsource (lib "eagle-import") (part "RESISTOR0805-RES"))
    )
    (comp (ref "R55")
      (value "100K")
      (footprint "eagle-import:0805")
      (libsource (lib "eagle-import") (part "RESISTOR0805-RES"))
    )
    (comp (ref "R59")
      (value "2.2K")
      (footprint "eagle-import:0805")
      (libsource (lib "eagle-import") (part "RESISTOR0805-RES"))
    )
    (comp (ref "R60")
      (value "100K")
      (footprint "eagle-import:0805")
      (libsource (lib "eagle-import") (part "RESISTOR0805-RES"))
    )
    (comp (ref "R61")
      (value "2.2K")
      (footprint "eagle-import:0805")
      (libsource (lib "eagle-import") (part "RESISTOR0805-RES"))
    )
    (comp (ref "R68")
      (value "1K")
      (footprint "eagle-import:0805")
      (libsource (lib "eagle-import") (part "RESISTOR0805-RES"))
    )
    (comp (ref "R69")
      (value "8.2K")
      (footprint "eagle-import:0805")
      (libsource (lib "eagle-import") (part "RESISTOR0805-RES"))
    )
    (comp (ref "R89")
      (value "10")
      (footprint "eagle-import:1206")
      (libsource (lib "eagle-import") (part "RESISTOR1206"))
    )
    (comp (ref "U1")
      (value "OKI6295")
      (footprint "eagle-import:OKI6295")
      (libsource (lib "eagle-import") (part "OKI6295"))
    )
    (comp (ref "U12")
      (value "27C040-150")
      (footprint "eagle-import:27C040")
      (libsource (lib "eagle-import") (part "27C040"))
    )
    (comp (ref "U13")
      (value "27C040-150")
      (footprint "eagle-import:27C040")
      (libsource (lib "eagle-import") (part "27C040"))
    )
    (comp (ref "U14")
      (value "YAMAHA 2151")
      (footprint "eagle-import:YM2151")
      (libsource (lib "eagle-import") (part "YM2151"))
    )
    (comp (ref "U15")
      (value "TIL7524")
      (footprint "eagle-import:SOIC16N")
      (fields (field (name "MF") "ALTERA CORPORATION") (field (name "MPN") "AD7524JRZ"))
      (libsource (lib "eagle-import") (part "AD7524RJ"))
    )
    (comp (ref "U17")
      (value "74LS174")
      (footprint "eagle-import:SO16")
      (libsource (lib "eagle-import") (part "74174DLS"))
    )
    (comp (ref "U19")
      (value "74LS11")
      (footprint "eagle-import:SO14")
      (libsource (lib "eagle-import") (part "7411DLS"))
    )
    (comp (ref "U26")
      (value "74LS04")
      (footprint "eagle-import:SO14")
      (libsource (lib "eagle-import") (part "7404DLS"))
    )
    (comp (ref "U28")
      (value "YAMAHA 3012")
      (footprint "eagle-import:YM3012")
      (libsource (lib "eagle-import") (part "YM3012"))
    )
    (comp (ref "U29")
      (value "LM324D")
      (footprint "eagle-import:SO14")
      (libsource (lib "eagle-import") (part "LM324D"))
    )
    (comp (ref "W7")
      (value "JUMPER")
      (footprint "eagle-import:SJ")
      (libsource (lib "eagle-import") (part "SJ"))
    )
    (comp (ref "Y1")
      (value "3.5749MHz")
      (footprint "eagle-import:SM49")
      (fields (field (name "TOLERANCE") "0.01%"))
      (libsource (lib "eagle-import") (part "CRYSTALSM49"))
    )
    (comp (ref "C3")
      (value ".01uF")
      (footprint "eagle-import:0805")
      (fields (field (name "VOLTAGE") "50V"))
      (libsource (lib "eagle-import") (part "CAP0805"))
    )
    (comp (ref "C6")
      (value ".01uF")
      (footprint "eagle-import:0805")
      (fields (field (name "VOLTAGE") "50V"))
      (libsource (lib "eagle-import") (part "CAP0805"))
    )
    (comp (ref "C7")
      (value ".01uF")
      (footprint "eagle-import:0805")
      (fields (field (name "VOLTAGE") "50V"))
      (libsource (lib "eagle-import") (part "CAP0805"))
    )
    (comp (ref "C62")
      (value "68pF")
      (footprint "eagle-import:0805")
      (libsource (lib "eagle-import") (part "CAP0805"))
    )
    (comp (ref "C100")
      (value "10uF")
      (footprint "eagle-import:PANASONIC_C")
      (fields (field (name "VOLTAGE") "20V"))
      (libsource (lib "eagle-import") (part "CAP_POLC"))
    )
    (comp (ref "CR1")
      (value "1N4148")
      (footprint "eagle-import:SMA-DIODE")
      (libsource (lib "eagle-import") (part "DIODESMA"))
    )
    (comp (ref "MTG1")
      (value "MTGHOLE")
      (footprint "eagle-import:STANDOFF-ELECTRICAL")
      (libsource (lib "eagle-import") (part "STANDOFF_ELECTRICAL"))
    )
    (comp (ref "MTG2")
      (value "MTGHOLE")
      (footprint "eagle-import:STANDOFF-ELECTRICAL")
      (libsource (lib "eagle-import") (part "STANDOFF_ELECTRICAL"))
    )
    (comp (ref "MTG3")
      (value "MTGHOLE")
      (footprint "eagle-import:STANDOFF-ELECTRICAL")
      (libsource (lib "eagle-import") (part "STANDOFF_ELECTRICAL"))
    )
    (comp (ref "MTG4")
      (value "MTGHOLE")
      (footprint "eagle-import:STANDOFF-ELECTRICAL")
      (libsource (lib "eagle-import") (part "STANDOFF_ELECTRICAL"))
    )
    (comp (ref "P4")
      (value "ORKIN R/W")
      (footprint "eagle-import:1X04_LONGPADS")
      (fields (field (name "PITCH") "0.100\""))
      (libsource (lib "eagle-import") (part "M04LONGPADS"))
    )
    (comp (ref "Q1")
      (value "MPS3646")
      (footprint "eagle-import:SOT23-3")
      (libsource (lib "eagle-import") (part "TRANSISTOR_NPNMMBT2222A"))
    )
    (comp (ref "R1")
      (value "4.7K")
      (footprint "eagle-import:0805")
      (libsource (lib "eagle-import") (part "RESISTOR0805-RES"))
    )
    (comp (ref "R2")
      (value "4.7K")
      (footprint "eagle-import:0805")
      (libsource (lib "eagle-import") (part "RESISTOR0805-RES"))
    )
    (comp (ref "R3")
      (value "4.7K")
      (footprint "eagle-import:0805")
      (libsource (lib "eagle-import") (part "RESISTOR0805-RES"))
    )
    (comp (ref "R5")
      (value "4.7K")
      (footprint "eagle-import:0805")
      (libsource (lib "eagle-import") (part "RESISTOR0805-RES"))
    )
    (comp (ref "R6")
      (value "4.7K")
      (footprint "eagle-import:0805")
      (libsource (lib "eagle-import") (part "RESISTOR0805-RES"))
    )
    (comp (ref "R7")
      (value "4.7K")
      (footprint "eagle-import:0805")
      (libsource (lib "eagle-import") (part "RESISTOR0805-RES"))
    )
    (comp (ref "R8")
      (value "4.7K")
      (footprint "eagle-import:R1206")
      (libsource (lib "eagle-import") (part "R-US_R1206"))
    )
    (comp (ref "R9")
      (value "4.7K")
      (footprint "eagle-import:0805")
      (libsource (lib "eagle-import") (part "RESISTOR0805-RES"))
    )
    (comp (ref "R10")
      (value "4.7K")
      (footprint "eagle-import:0805")
      (libsource (lib "eagle-import") (part "RESISTOR0805-RES"))
    )
    (comp (ref "R22")
      (value "2.2K")
      (footprint "eagle-import:0805")
      (libsource (lib "eagle-import") (part "RESISTOR0805-RES"))
    )
    (comp (ref "R23")
      (value "2.2K")
      (footprint "eagle-import:0805")
      (libsource (lib "eagle-import") (part "RESISTOR0805-RES"))
    )
    (comp (ref "R24")
      (value "2.2K")
      (footprint "eagle-import:0805")
      (libsource (lib "eagle-import") (part "RESISTOR0805-RES"))
    )
    (comp (ref "R25")
      (value "4.7K")
      (footprint "eagle-import:0805")
      (libsource (lib "eagle-import") (part "RESISTOR0805-RES"))
    )
    (comp (ref "R26")
      (value "2.2K")
      (footprint "eagle-import:0805")
      (libsource (lib "eagle-import") (part "RESISTOR0805-RES"))
    )
    (comp (ref "R27")
      (value "150")
      (footprint "eagle-import:1206")
      (libsource (lib "eagle-import") (part "RESISTOR1206"))
    )
    (comp (ref "R28")
      (value "3.3K")
      (footprint "eagle-import:0805")
      (libsource (lib "eagle-import") (part "RESISTOR0805-RES"))
    )
    (comp (ref "R29")
      (value "47K")
      (footprint "eagle-import:0805")
      (libsource (lib "eagle-import") (part "RESISTOR0805-RES"))
    )
    (comp (ref "R30")
      (value "100")
      (footprint "eagle-import:1206")
      (libsource (lib "eagle-import") (part "RESISTOR1206"))
    )
    (comp (ref "R91")
      (value "4.7K")
      (footprint "eagle-import:0805")
      (libsource (lib "eagle-import") (part "RESISTOR0805-RES"))
    )
    (comp (ref "U2")
      (value "2064")
      (footprint "eagle-import:MS6264L")
      (libsource (lib "eagle-import") (part "MS6264L"))
    )
    (comp (ref "U3")
      (value "27C040")
      (footprint "eagle-import:27C040")
      (libsource (lib "eagle-import") (part "27C040"))
    )
    (comp (ref "U4")
      (value "6809E")
      (footprint "eagle-import:DIP40")
      (libsource (lib "eagle-import") (part "6809E"))
    )
    (comp (ref "U8")
      (value "74LS138")
      (footprint "eagle-import:SO16")
      (libsource (lib "eagle-import") (part "74138DLS"))
    )
    (comp (ref "U16")
      (value "74LS374")
      (footprint "eagle-import:SO20W")
      (libsource (lib "eagle-import") (part "74374DWLS"))
    )
    (comp (ref "U18")
      (value "16L8")
      (footprint "eagle-import:16L8")
      (libsource (lib "eagle-import") (part "PAL16L8"))
    )
    (comp (ref "U20")
      (value "74LS139")
      (footprint "eagle-import:SO16")
      (libsource (lib "eagle-import") (part "74139DLS"))
    )
    (comp (ref "U21")
      (value "74LS14")
      (footprint "eagle-import:SO14")
      (libsource (lib "eagle-import") (part "7414DLS"))
    )
    (comp (ref "U22")
      (value "74LS74")
      (footprint "eagle-import:SO14")
      (libsource (lib "eagle-import") (part "7474DLS"))
    )
    (comp (ref "W1")
      (value "JUMPER")
      (footprint "eagle-import:SJ")
      (libsource (lib "eagle-import") (part "SJ"))
    )
    (comp (ref "W2")
      (value "JUMPER")
      (footprint "eagle-import:SJ")
      (libsource (lib "eagle-import") (part "SJ"))
    )
    (comp (ref "W3")
      (value "JUMPER")
      (footprint "eagle-import:SJ")
      (libsource (lib "eagle-import") (part "SJ"))
    )
    (comp (ref "W4")
      (value "JUMPER")
      (footprint "eagle-import:SJ")
      (libsource (lib "eagle-import") (part "SJ"))
    )
    (comp (ref "W5")
      (value "JUMPER")
      (footprint "eagle-import:SJ")
      (libsource (lib "eagle-import") (part "SJ"))
    )
    (comp (ref "W6")
      (value "JUMPER")
      (footprint "eagle-import:SJ")
      (libsource (lib "eagle-import") (part "SJ"))
    )
    (comp (ref "Y2")
      (value "8MHz")
      (footprint "eagle-import:CRYSTAL-OSC-SMD-5X3")
      (fields (field (name "TOLERANCE") "0.01%"))
      (libsource (lib "eagle-import") (part "OSCILLATOR5X3-PIN1-INDICATED"))
    )
  )
  (nets
    (net (code "1") (name "+9V") (class "Default")
      (node (ref "C65") (pin "2") (pinfunction "2_2") (pintype "passive"))
      (node (ref "U30") (pin "8") (pinfunction "VCC_8") (pintype "power_in"))
      (node (ref "VR1") (pin "3") (pinfunction "OUT_3") (pintype "passive"))
    )
    (net (code "2") (name "+12VDEC") (class "Default")
      (node (ref "C102") (pin "+") (pinfunction "+_+") (pintype "passive"))
      (node (ref "R48") (pin "2") (pinfunction "2_2") (pintype "passive"))
      (node (ref "R55") (pin "2") (pinfunction "2_2") (pintype "passive"))
      (node (ref "R90") (pin "1") (pinfunction "1_1") (pintype "passive"))
    )
    (net (code "3") (name "5V") (class "Default")
      (node (ref "C10") (pin "1") (pinfunction "1_1") (pintype "passive"))
      (node (ref "C11") (pin "1") (pinfunction "1_1") (pintype "passive"))
      (node (ref "C12") (pin "1") (pinfunction "1_1") (pintype "passive"))
      (node (ref "C13") (pin "1") (pinfunction "1_1") (pintype "passive"))
      (node (ref "C14") (pin "1") (pinfunction "1_1") (pintype "passive"))
      (node (ref "C15") (pin "1") (pinfunction "1_1") (pintype "passive"))
      (node (ref "C16") (pin "1") (pinfunction "1_1") (pintype "passive"))
      (node (ref "C17") (pin "1") (pinfunction "1_1") (pintype "passive"))
      (node (ref "C18") (pin "1") (pinfunction "1_1") (pintype "passive"))
      (node (ref "C19") (pin "1") (pinfunction "1_1") (pintype "passive"))
      (node (ref "C2") (pin "1") (pinfunction "1_1") (pintype "passive"))
      (node (ref "C20") (pin "1") (pinfunction "1_1") (pintype "passive"))
      (node (ref "C21") (pin "1") (pinfunction "1_1") (pintype "passive"))
      (node (ref "C22") (pin "1") (pinfunction "1_1") (pintype "passive"))
      (node (ref "C23") (pin "1") (pinfunction "1_1") (pintype "passive"))
      (node (ref "C24") (pin "1") (pinfunction "1_1") (pintype "passive"))
      (node (ref "C25") (pin "1") (pinfunction "1_1") (pintype "passive"))
      (node (ref "C26") (pin "1") (pinfunction "1_1") (pintype "passive"))
      (node (ref "C28") (pin "1") (pinfunction "1_1") (pintype "passive"))
      (node (ref "C3") (pin "1") (pinfunction "1_1") (pintype "passive"))
      (node (ref "C4") (pin "1") (pinfunction "1_1") (pintype "passive"))
      (node (ref "C5") (pin "1") (pinfunction "1_1") (pintype "passive"))
      (node (ref "C6") (pin "1") (pinfunction "1_1") (pintype "passive"))
      (node (ref "C7") (pin "1") (pinfunction "1_1") (pintype "passive"))
      (node (ref "C70") (pin "+") (pinfunction "+_+") (pintype "passive"))
      (node (ref "C72") (pin "1") (pinfunction "1_1") (pintype "passive"))
      (node (ref "C8") (pin "1") (pinfunction "1_1") (pintype "passive"))
      (node (ref "C9") (pin "1") (pinfunction "1_1") (pintype "passive"))
      (node (ref "L1") (pin "1") (pinfunction "1_1") (pintype "passive"))
      (node (ref "R1") (pin "2") (pinfunction "2_2") (pintype "passive"))
      (node (ref "R10") (pin "2") (pinfunction "2_2") (pintype "passive"))
      (node (ref "R2") (pin "2") (pinfunction "2_2") (pintype "passive"))
      (node (ref "R22") (pin "2") (pinfunction "2_2") (pintype "passive"))
      (node (ref "R23") (pin "2") (pinfunction "2_2") (pintype "passive"))
      (node (ref "R24") (pin "2") (pinfunction "2_2") (pintype "passive"))
      (node (ref "R25") (pin "2") (pinfunction "2_2") (pintype "passive"))
      (node (ref "R26") (pin "2") (pinfunction "2_2") (pintype "passive"))
      (node (ref "R27") (pin "2") (pinfunction "2_2") (pintype "passive"))
      (node (ref "R29") (pin "2") (pinfunction "2_2") (pintype "passive"))
      (node (ref "R3") (pin "2") (pinfunction "2_2") (pintype "passive"))
      (node (ref "R30") (pin "2") (pinfunction "2_2") (pintype "passive"))
      (node (ref "R5") (pin "2") (pinfunction "2_2") (pintype "passive"))
      (node (ref "R6") (pin "2") (pinfunction "2_2") (pintype "passive"))
      (node (ref "R69") (pin "2") (pinfunction "2_2") (pintype "passive"))
      (node (ref "R7") (pin "2") (pinfunction "2_2") (pintype "passive"))
      (node (ref "R8") (pin "2") (pinfunction "2_2") (pintype "passive"))
      (node (ref "R82") (pin "2") (pinfunction "2_2") (pintype "passive"))
      (node (ref "R84") (pin "2") (pinfunction "2_2") (pintype "passive"))
      (node (ref "R85") (pin "2") (pinfunction "2_2") (pintype "passive"))
      (node (ref "R86") (pin "2") (pinfunction "2_2") (pintype "passive"))
      (node (ref "R89") (pin "2") (pinfunction "2_2") (pintype "passive"))
      (node (ref "R9") (pin "2") (pinfunction "2_2") (pintype "passive"))
      (node (ref "R91") (pin "2") (pinfunction "2_2") (pintype "passive"))
      (node (ref "U1") (pin "7") (pinfunction "SS_7") (pintype "passive"))
      (node (ref "U10") (pin "16") (pinfunction "VCC_16") (pintype "power_in"))
      (node (ref "U11") (pin "16") (pinfunction "VCC_16") (pintype "power_in"))
      (node (ref "U12") (pin "1") (pinfunction "VPP_1") (pintype "passive"))
      (node (ref "U12") (pin "32") (pinfunction "VCC_32") (pintype "passive"))
      (node (ref "U13") (pin "1") (pinfunction "VPP_1") (pintype "passive"))
      (node (ref "U13") (pin "32") (pinfunction "VCC_32") (pintype "passive"))
      (node (ref "U14") (pin "22") (pinfunction "VDD_22") (pintype "passive"))
      (node (ref "U15") (pin "14") (pinfunction "VDD_14") (pintype "power_in"))
      (node (ref "U16") (pin "20") (pinfunction "VCC_20") (pintype "power_in"))
      (node (ref "U17") (pin "16") (pinfunction "VCC_16") (pintype "power_in"))
      (node (ref "U18") (pin "20") (pinfunction "VCC_20") (pintype "passive"))
      (node (ref "U19") (pin "14") (pinfunction "VCC_14") (pintype "power_in"))
      (node (ref "U2") (pin "28") (pinfunction "VCC_28") (pintype "power_in"))
      (node (ref "U20") (pin "16") (pinfunction "VCC_16") (pintype "power_in"))
      (node (ref "U21") (pin "14") (pinfunction "VCC_14") (pintype "power_in"))
      (node (ref "U22") (pin "14") (pinfunction "VCC_14") (pintype "power_in"))
      (node (ref "U23") (pin "14") (pinfunction "VCC_14") (pintype "power_in"))
      (node (ref "U24") (pin "16") (pinfunction "VCC_16") (pintype "power_in"))
      (node (ref "U25") (pin "16") (pinfunction "VCC_16") (pintype "power_in"))
      (node (ref "U26") (pin "14") (pinfunction "VCC_14") (pintype "power_in"))
      (node (ref "U28") (pin "1") (pinfunction "VDD_1") (pintype "passive"))
      (node (ref "U3") (pin "1") (pinfunction "VPP_1") (pintype "passive"))
      (node (ref "U3") (pin "32") (pinfunction "VCC_32") (pintype "passive"))
      (node (ref "U5") (pin "20") (pinfunction "VCC_20") (pintype "power_in"))
      (node (ref "U6") (pin "16") (pinfunction "VCC_16") (pintype "power_in"))
      (node (ref "U7") (pin "16") (pinfunction "VCC_16") (pintype "power_in"))
      (node (ref "U8") (pin "16") (pinfunction "VCC_16") (pintype "power_in"))
      (node (ref "U8") (pin "6") (pinfunction "G1_6") (pintype "input"))
      (node (ref "U9") (pin "14") (pinfunction "VCC_14") (pintype "power_in"))
      (node (ref "Y2") (pin "4") (pinfunction "VCC_4") (pintype "bidirectional"))
    )
    (net (code "4") (name "12V") (class "Default")
      (node (ref "C29") (pin "1") (pinfunction "1_1") (pintype "passive"))
      (node (ref "C31") (pin "1") (pinfunction "1_1") (pintype "passive"))
      (node (ref "C32") (pin "2") (pinfunction "2_2") (pintype "passive"))
      (node (ref "C33") (pin "1") (pinfunction "1_1") (pintype "passive"))
      (node (ref "C85") (pin "+") (pinfunction "+_+") (pintype "passive"))
      (node (ref "C89") (pin "1") (pinfunction "1_1") (pintype "passive"))
      (node (ref "C95") (pin "1") (pinfunction "+_1") (pintype "passive"))
      (node (ref "L2") (pin "2") (pinfunction "2_2") (pintype "passive"))
      (node (ref "R54") (pin "1") (pinfunction "1_1") (pintype "passive"))
      (node (ref "R90") (pin "2") (pinfunction "2_2") (pintype "passive"))
      (node (ref "U29") (pin "4") (pinfunction "V+_4") (pintype "power_in"))
      (node (ref "U31") (pin "11") (pinfunction "VCC_11") (pintype "power_in"))
      (node (ref "U32") (pin "4") (pinfunction "V+_4") (pintype "power_in"))
      (node (ref "U33") (pin "4") (pinfunction "V+_4") (pintype "power_in"))
      (node (ref "VR1") (pin "1") (pinfunction "IN_1") (pintype "input"))
    )
    (net (code "5") (name "A0") (class "Default")
      (node (ref "U14") (pin "4") (pinfunction "A0_4") (pintype "passive"))
      (node (ref "U2") (pin "10") (pinfunction "A0_10") (pintype "input"))
      (node (ref "U3") (pin "12") (pinfunction "A0_12") (pintype "passive"))
      (node (ref "U4") (pin "8") (pinfunction "A0_8") (pintype "passive"))
    )
    (net (code "6") (name "A1") (class "Default")
      (node (ref "U2") (pin "9") (pinfunction "A1_9") (pintype "input"))
      (node (ref "U3") (pin "11") (pinfunction "A1_11") (pintype "passive"))
      (node (ref "U4") (pin "9") (pinfunction "A1_9") (pintype "passive"))
    )
    (net (code "7") (name "A2") (class "Default")
      (node (ref "U2") (pin "8") (pinfunction "A2_8") (pintype "input"))
      (node (ref "U3") (pin "10") (pinfunction "A2_10") (pintype "passive"))
      (node (ref "U4") (pin "10") (pinfunction "A2_10") (pintype "passive"))
    )
    (net (code "8") (name "A3") (class "Default")
      (node (ref "U2") (pin "7") (pinfunction "A3_7") (pintype "input"))
      (node (ref "U3") (pin "9") (pinfunction "A3_9") (pintype "passive"))
      (node (ref "U4") (pin "11") (pinfunction "A3_11") (pintype "passive"))
    )
    (net (code "9") (name "A4") (class "Default")
      (node (ref "U2") (pin "6") (pinfunction "A4_6") (pintype "input"))
      (node (ref "U3") (pin "8") (pinfunction "A4_8") (pintype "passive"))
      (node (ref "U4") (pin "12") (pinfunction "A4_12") (pintype "passive"))
    )
    (net (code "10") (name "A5") (class "Default")
      (node (ref "U2") (pin "5") (pinfunction "A5_5") (pintype "input"))
      (node (ref "U3") (pin "7") (pinfunction "A5_7") (pintype "passive"))
      (node (ref "U4") (pin "13") (pinfunction "A5_13") (pintype "passive"))
    )
    (net (code "11") (name "A6") (class "Default")
      (node (ref "U2") (pin "4") (pinfunction "A6_4") (pintype "input"))
      (node (ref "U3") (pin "6") (pinfunction "A6_6") (pintype "passive"))
      (node (ref "U4") (pin "14") (pinfunction "A6_14") (pintype "passive"))
    )
    (net (code "12") (name "A7") (class "Default")
      (node (ref "U2") (pin "3") (pinfunction "A7_3") (pintype "input"))
      (node (ref "U3") (pin "5") (pinfunction "A7_5") (pintype "passive"))
      (node (ref "U4") (pin "15") (pinfunction "A7_15") (pintype "passive"))
    )
    (net (code "13") (name "A8") (class "Default")
      (node (ref "U2") (pin "25") (pinfunction "A8_25") (pintype "input"))
      (node (ref "U3") (pin "27") (pinfunction "A8_27") (pintype "passive"))
      (node (ref "U4") (pin "16") (pinfunction "A8_16") (pintype "passive"))
    )
    (net (code "14") (name "A9") (class "Default")
      (node (ref "U2") (pin "24") (pinfunction "A9_24") (pintype "input"))
      (node (ref "U3") (pin "26") (pinfunction "A9_26") (pintype "passive"))
      (node (ref "U4") (pin "17") (pinfunction "A9_17") (pintype "passive"))
    )
    (net (code "15") (name "A10") (class "Default")
      (node (ref "U2") (pin "21") (pinfunction "A10_21") (pintype "input"))
      (node (ref "U3") (pin "23") (pinfunction "A10_23") (pintype "passive"))
      (node (ref "U4") (pin "18") (pinfunction "A10_18") (pintype "passive"))
      (node (ref "U8") (pin "1") (pinfunction "A_1") (pintype "input"))
    )
    (net (code "16") (name "A11") (class "Default")
      (node (ref "U2") (pin "23") (pinfunction "A11_23") (pintype "input"))
      (node (ref "U3") (pin "25") (pinfunction "A11_25") (pintype "passive"))
      (node (ref "U4") (pin "19") (pinfunction "A11_19") (pintype "passive"))
      (node (ref "U8") (pin "2") (pinfunction "B_2") (pintype "input"))
    )
    (net (code "17") (name "A12") (class "Default")
      (node (ref "U2") (pin "2") (pinfunction "A12_2") (pintype "input"))
      (node (ref "U3") (pin "4") (pinfunction "A12_4") (pintype "passive"))
      (node (ref "U4") (pin "20") (pinfunction "A12_20") (pintype "passive"))
      (node (ref "U8") (pin "3") (pinfunction "C_3") (pintype "input"))
    )
    (net (code "18") (name "A13") (class "Default")
      (node (ref "U20") (pin "14") (pinfunction "A_14") (pintype "input"))
      (node (ref "U3") (pin "28") (pinfunction "A13_28") (pintype "passive"))
      (node (ref "U4") (pin "21") (pinfunction "A13_21") (pintype "passive"))
    )
    (net (code "19") (name "A14") (class "Default")
      (node (ref "U20") (pin "2") (pinfunction "A_2") (pintype "input"))
      (node (ref "U4") (pin "22") (pinfunction "A14_22") (pintype "passive"))
    )
    (net (code "20") (name "A15") (class "Default")
      (node (ref "U20") (pin "3") (pinfunction "B_3") (pintype "input"))
      (node (ref "U4") (pin "23") (pinfunction "A15_23") (pintype "passive"))
      (node (ref "W4") (pin "1") (pinfunction "1_1") (pintype "passive"))
      (node (ref "W5") (pin "1") (pinfunction "1_1") (pintype "passive"))
    )
    (net (code "21") (name "ADPCM") (class "Default")
      (node (ref "U1") (pin "4") (pinfunction "~{CS}_4") (pintype "passive"))
      (node (ref "U8") (pin "12") (pinfunction "Y3_12") (pintype "output"))
    )
    (net (code "22") (name "ADPCMCLK") (class "Default")
      (node (ref "U1") (pin "5") (pinfunction "XTAL_5") (pintype "passive"))
      (node (ref "U9") (pin "5") (pinfunction "Q_5") (pintype "output"))
    )
    (net (code "23") (name "AGND") (class "Default")
      (node (ref "C102") (pin "-") (pinfunction "-_-") (pintype "passive"))
      (node (ref "C29") (pin "2") (pinfunction "2_2") (pintype "passive"))
      (node (ref "C31") (pin "2") (pinfunction "2_2") (pintype "passive"))
      (node (ref "C32") (pin "1") (pinfunction "1_1") (pintype "passive"))
      (node (ref "C33") (pin "2") (pinfunction "2_2") (pintype "passive"))
      (node (ref "C48") (pin "2") (pinfunction "2_2") (pintype "passive"))
      (node (ref "C50") (pin "2") (pinfunction "2_2") (pintype "passive"))
      (node (ref "C51") (pin "2") (pinfunction "2_2") (pintype "passive"))
      (node (ref "C54") (pin "2") (pinfunction "2_2") (pintype "passive"))
      (node (ref "C56") (pin "2") (pinfunction "2_2") (pintype "passive"))
      (node (ref "C61") (pin "2") (pinfunction "2_2") (pintype "passive"))
      (node (ref "C63") (pin "-") (pinfunction "-_-") (pintype "passive"))
      (node (ref "C64") (pin "-") (pinfunction "-_-") (pintype "passive"))
      (node (ref "C65") (pin "1") (pinfunction "1_1") (pintype "passive"))
      (node (ref "C66") (pin "-") (pinfunction "-_-") (pintype "passive"))
      (node (ref "C69") (pin "2") (pinfunction "2_2") (pintype "passive"))
      (node (ref "C73") (pin "-") (pinfunction "-_-") (pintype "passive"))
      (node (ref "C76") (pin "2") (pinfunction "2_2") (pintype "passive"))
      (node (ref "C80") (pin "-") (pinfunction "-_-") (pintype "passive"))
      (node (ref "C83") (pin "-") (pinfunction "-_-") (pintype "passive"))
      (node (ref "C84") (pin "-") (pinfunction "-_-") (pintype "passive"))
      (node (ref "C85") (pin "-") (pinfunction "-_-") (pintype "passive"))
      (node (ref "C88") (pin "2") (pinfunction "2_2") (pintype "passive"))
      (node (ref "C89") (pin "2") (pinfunction "2_2") (pintype "passive"))
      (node (ref "C90") (pin "1") (pinfunction "1_1") (pintype "passive"))
      (node (ref "C91") (pin "1") (pinfunction "1_1") (pintype "passive"))
      (node (ref "C95") (pin "2") (pinfunction "-_2") (pintype "passive"))
      (node (ref "C97") (pin "1") (pinfunction "1_1") (pintype "passive"))
      (node (ref "C98") (pin "2") (pinfunction "2_2") (pintype "passive"))
      (node (ref "CR2") (pin "1") (pinfunction "A_1") (pintype "passive"))
      (node (ref "P2") (pin "1") (pinfunction "1_1") (pintype "passive"))
      (node (ref "P3") (pin "1") (pinfunction "1_1") (pintype "passive"))
      (node (ref "P5") (pin "4") (pinfunction "4_4") (pintype "passive"))
      (node (ref "R33") (pin "1") (pinfunction "1_1") (pintype "passive"))
      (node (ref "R37") (pin "1") (pinfunction "1_1") (pintype "passive"))
      (node (ref "R41") (pin "1") (pinfunction "1_1") (pintype "passive"))
      (node (ref "R42") (pin "1") (pinfunction "1_1") (pintype "passive"))
      (node (ref "R59") (pin "1") (pinfunction "1_1") (pintype "passive"))
      (node (ref "R60") (pin "1") (pinfunction "1_1") (pintype "passive"))
      (node (ref "R61") (pin "1") (pinfunction "1_1") (pintype "passive"))
      (node (ref "R68") (pin "1") (pinfunction "1_1") (pintype "passive"))
      (node (ref "R70") (pin "2") (pinfunction "2_2") (pintype "passive"))
      (node (ref "U15") (pin "2") (pinfunction "OUT2_2") (pintype "passive"))
      (node (ref "U28") (pin "16") (pinfunction "AGND-16_16") (pintype "passive"))
      (node (ref "U28") (pin "8") (pinfunction "AGND-8_8") (pintype "passive"))
      (node (ref "U29") (pin "11") (pinfunction "V-_11") (pintype "power_in"))
      (node (ref "U30") (pin "3") (pinfunction "GND_3") (pintype "power_in"))
      (node (ref "U31") (pin "3") (pinfunction "GND_IN_3") (pintype "power_in"))
      (node (ref "U31") (pin "7") (pinfunction "GND_OUT_7") (pintype "passive"))
      (node (ref "U32") (pin "11") (pinfunction "V-_11") (pintype "power_in"))
      (node (ref "U33") (pin "11") (pinfunction "V-_11") (pintype "power_in"))
      (node (ref "VR1") (pin "2") (pinfunction "REF_2") (pintype "passive"))
      (node (ref "W8") (pin "2") (pinfunction "2_2") (pintype "passive"))
    )
    (net (code "24") (name "ATE1") (class "Default")
      (node (ref "R25") (pin "1") (pinfunction "1_1") (pintype "passive"))
      (node (ref "U16") (pin "13") (pinfunction "5D_13") (pintype "input"))
      (node (ref "U16") (pin "14") (pinfunction "6D_14") (pintype "input"))
      (node (ref "U16") (pin "17") (pinfunction "7D_17") (pintype "input"))
      (node (ref "U16") (pin "18") (pinfunction "8D_18") (pintype "input"))
      (node (ref "U17") (pin "11") (pinfunction "D4_11") (pintype "input"))
      (node (ref "U17") (pin "13") (pinfunction "D5_13") (pintype "input"))
      (node (ref "U17") (pin "3") (pinfunction "D1_3") (pintype "input"))
      (node (ref "U18") (pin "8") (pinfunction "8-IN_8") (pintype "passive"))
      (node (ref "U19") (pin "9") (pinfunction "I0_9") (pintype "input"))
      (node (ref "U23") (pin "13") (pinfunction "CLR_13") (pintype "input"))
      (node (ref "U24") (pin "4") (pinfunction "EN_4") (pintype "bidirectional"))
      (node (ref "U24") (pin "9") (pinfunction "INC_9") (pintype "input"))
      (node (ref "U25") (pin "4") (pinfunction "EN_4") (pintype "bidirectional"))
      (node (ref "U9") (pin "10") (pinfunction "PRE_10") (pintype "input"))
      (node (ref "U9") (pin "12") (pinfunction "D_12") (pintype "input"))
    )
    (net (code "25") (name "ATE_CLR") (class "Default")
      (node (ref "R9") (pin "1") (pinfunction "1_1") (pintype "passive"))
      (node (ref "U17") (pin "1") (pinfunction "CLR_1") (pintype "input"))
      (node (ref "U22") (pin "1") (pinfunction "CLR_1") (pintype "input"))
      (node (ref "U22") (pin "13") (pinfunction "CLR_13") (pintype "input"))
      (node (ref "U23") (pin "1") (pinfunction "CLR_1") (pintype "input"))
      (node (ref "U9") (pin "1") (pinfunction "CLR_1") (pintype "input"))
    )
    (net (code "26") (name "BS0") (class "Default")
      (node (ref "U17") (pin "5") (pinfunction "Q2_5") (pintype "output"))
      (node (ref "U18") (pin "1") (pinfunction "1-IN_1") (pintype "passive"))
    )
    (net (code "27") (name "BS1") (class "Default")
      (node (ref "U17") (pin "15") (pinfunction "Q6_15") (pintype "output"))
      (node (ref "U18") (pin "2") (pinfunction "2-IN_2") (pintype "passive"))
    )
    (net (code "28") (name "BS2") (class "Default")
      (node (ref "U17") (pin "7") (pinfunction "Q3_7") (pintype "output"))
      (node (ref "U18") (pin "3") (pinfunction "3-IN_3") (pintype "passive"))
      (node (ref "U19") (pin "10") (pinfunction "I1_10") (pintype "input"))
    )
    (net (code "29") (name "B_SND_RD") (class "Default")
      (node (ref "C44") (pin "1") (pinfunction "1_1") (pintype "passive"))
      (node (ref "P1") (pin "15") (pinfunction "15_15") (pintype "passive"))
      (node (ref "R20") (pin "2") (pinfunction "2_2") (pintype "passive"))
    )
    (net (code "30") (name "B_VIDDAV") (class "Default")
      (node (ref "C104") (pin "2") (pinfunction "2_2") (pintype "passive"))
      (node (ref "R96") (pin "1") (pinfunction "1_1") (pintype "passive"))
      (node (ref "U25") (pin "14") (pinfunction "IND_14") (pintype "bidirectional"))
    )
    (net (code "31") (name "B_VIDRES") (class "Default")
      (node (ref "C106") (pin "1") (pinfunction "1_1") (pintype "passive"))
      (node (ref "R85") (pin "1") (pinfunction "1_1") (pintype "passive"))
      (node (ref "R93") (pin "1") (pinfunction "1_1") (pintype "passive"))
      (node (ref "U25") (pin "6") (pinfunction "INB_6") (pintype "bidirectional"))
    )
    (net (code "32") (name "D0") (class "Default")
      (node (ref "U1") (pin "37") (pinfunction "D0_37") (pintype "passive"))
      (node (ref "U14") (pin "10") (pinfunction "D0_10") (pintype "passive"))
      (node (ref "U15") (pin "11") (pinfunction "D0_11") (pintype "input"))
      (node (ref "U16") (pin "3") (pinfunction "1D_3") (pintype "input"))
      (node (ref "U17") (pin "4") (pinfunction "D2_4") (pintype "input"))
      (node (ref "U2") (pin "11") (pinfunction "I/O0_11") (pintype "bidirectional"))
      (node (ref "U3") (pin "13") (pinfunction "D0_13") (pintype "passive"))
      (node (ref "U4") (pin "31") (pinfunction "D0_31") (pintype "passive"))
      (node (ref "U5") (pin "3") (pinfunction "1D_3") (pintype "input"))
      (node (ref "U6") (pin "3") (pinfunction "OUTA_3") (pintype "bidirectional"))
    )
    (net (code "33") (name "D1") (class "Default")
      (node (ref "U1") (pin "38") (pinfunction "D1_38") (pintype "passive"))
      (node (ref "U14") (pin "12") (pinfunction "D1_12") (pintype "passive"))
      (node (ref "U15") (pin "10") (pinfunction "D1_10") (pintype "input"))
      (node (ref "U16") (pin "4") (pinfunction "2D_4") (pintype "input"))
      (node (ref "U17") (pin "14") (pinfunction "D6_14") (pintype "input"))
      (node (ref "U2") (pin "12") (pinfunction "I/O1_12") (pintype "bidirectional"))
      (node (ref "U3") (pin "14") (pinfunction "D1_14") (pintype "passive"))
      (node (ref "U4") (pin "30") (pinfunction "D1_30") (pintype "passive"))
      (node (ref "U5") (pin "4") (pinfunction "2D_4") (pintype "input"))
      (node (ref "U6") (pin "5") (pinfunction "OUTB_5") (pintype "bidirectional"))
    )
    (net (code "34") (name "D2") (class "Default")
      (node (ref "U1") (pin "39") (pinfunction "D2_39") (pintype "passive"))
      (node (ref "U14") (pin "13") (pinfunction "D2_13") (pintype "passive"))
      (node (ref "U15") (pin "9") (pinfunction "D2_9") (pintype "input"))
      (node (ref "U16") (pin "7") (pinfunction "3D_7") (pintype "input"))
      (node (ref "U17") (pin "6") (pinfunction "D3_6") (pintype "input"))
      (node (ref "U2") (pin "13") (pinfunction "I/O2_13") (pintype "bidirectional"))
      (node (ref "U3") (pin "15") (pinfunction "D2_15") (pintype "passive"))
      (node (ref "U4") (pin "29") (pinfunction "D2_29") (pintype "passive"))
      (node (ref "U5") (pin "7") (pinfunction "3D_7") (pintype "input"))
      (node (ref "U6") (pin "11") (pinfunction "OUTC_11") (pintype "bidirectional"))
    )
    (net (code "35") (name "D3") (class "Default")
      (node (ref "U1") (pin "40") (pinfunction "D3_40") (pintype "passive"))
      (node (ref "U14") (pin "14") (pinfunction "D3_14") (pintype "passive"))
      (node (ref "U15") (pin "8") (pinfunction "D3_8") (pintype "input"))
      (node (ref "U16") (pin "8") (pinfunction "4D_8") (pintype "input"))
      (node (ref "U2") (pin "15") (pinfunction "I/O3_15") (pintype "bidirectional"))
      (node (ref "U3") (pin "17") (pinfunction "D3_17") (pintype "passive"))
      (node (ref "U4") (pin "28") (pinfunction "D3_28") (pintype "passive"))
      (node (ref "U5") (pin "8") (pinfunction "4D_8") (pintype "input"))
      (node (ref "U6") (pin "13") (pinfunction "OUTD_13") (pintype "bidirectional"))
    )
    (net (code "36") (name "D4") (class "Default")
      (node (ref "U1") (pin "41") (pinfunction "D4_41") (pintype "passive"))
      (node (ref "U10") (pin "3") (pinfunction "OUTA_3") (pintype "bidirectional"))
      (node (ref "U14") (pin "15") (pinfunction "D4_15") (pintype "passive"))
      (node (ref "U15") (pin "7") (pinfunction "D4_7") (pintype "input"))
      (node (ref "U2") (pin "16") (pinfunction "I/O4_16") (pintype "bidirectional"))
      (node (ref "U3") (pin "18") (pinfunction "D4_18") (pintype "passive"))
      (node (ref "U4") (pin "27") (pinfunction "D4_27") (pintype "passive"))
      (node (ref "U5") (pin "13") (pinfunction "5D_13") (pintype "input"))
    )
    (net (code "37") (name "D5") (class "Default")
      (node (ref "U1") (pin "42") (pinfunction "D5_42") (pintype "passive"))
      (node (ref "U10") (pin "5") (pinfunction "OUTB_5") (pintype "bidirectional"))
      (node (ref "U14") (pin "16") (pinfunction "D5_16") (pintype "passive"))
      (node (ref "U15") (pin "6") (pinfunction "D5_6") (pintype "input"))
      (node (ref "U2") (pin "17") (pinfunction "I/O5_17") (pintype "bidirectional"))
      (node (ref "U3") (pin "19") (pinfunction "D5_19") (pintype "passive"))
      (node (ref "U4") (pin "26") (pinfunction "D5_26") (pintype "passive"))
      (node (ref "U5") (pin "14") (pinfunction "6D_14") (pintype "input"))
    )
    (net (code "38") (name "D6") (class "Default")
      (node (ref "U1") (pin "43") (pinfunction "D6_43") (pintype "passive"))
      (node (ref "U10") (pin "11") (pinfunction "OUTC_11") (pintype "bidirectional"))
      (node (ref "U14") (pin "17") (pinfunction "D6_17") (pintype "passive"))
      (node (ref "U15") (pin "5") (pinfunction "D6_5") (pintype "input"))
      (node (ref "U2") (pin "18") (pinfunction "I/O6_18") (pintype "bidirectional"))
      (node (ref "U3") (pin "20") (pinfunction "D6_20") (pintype "passive"))
      (node (ref "U4") (pin "25") (pinfunction "D6_25") (pintype "passive"))
      (node (ref "U5") (pin "17") (pinfunction "7D_17") (pintype "input"))
    )
    (net (code "39") (name "D7") (class "Default")
      (node (ref "U1") (pin "44") (pinfunction "D7_44") (pintype "passive"))
      (node (ref "U10") (pin "13") (pinfunction "OUTD_13") (pintype "bidirectional"))
      (node (ref "U14") (pin "18") (pinfunction "D7_18") (pintype "passive"))
      (node (ref "U15") (pin "4") (pinfunction "D7_4") (pintype "input"))
      (node (ref "U2") (pin "19") (pinfunction "I/O7_19") (pintype "bidirectional"))
      (node (ref "U3") (pin "21") (pinfunction "D7_21") (pintype "passive"))
      (node (ref "U4") (pin "24") (pinfunction "D7_24") (pintype "passive"))
      (node (ref "U5") (pin "18") (pinfunction "8D_18") (pintype "input"))
    )
    (net (code "40") (name "DAC") (class "Default")
      (node (ref "U15") (pin "12") (pinfunction "~{CS}_12") (pintype "input"))
      (node (ref "U8") (pin "13") (pinfunction "Y2_13") (pintype "output"))
    )
    (net (code "41") (name "DAC-OUT") (class "Default")
      (node (ref "R61") (pin "2") (pinfunction "2_2") (pintype "passive"))
      (node (ref "R62") (pin "2") (pinfunction "2_2") (pintype "passive"))
      (node (ref "U29") (pin "8") (pinfunction "OUT_8") (pintype "output"))
      (node (ref "U29") (pin "9") (pinfunction "-IN_9") (pintype "input"))
    )
    (net (code "42") (name "FFO") (class "Default")
      (node (ref "U24") (pin "1") (pinfunction "INA_1") (pintype "input"))
      (node (ref "U9") (pin "9") (pinfunction "Q_9") (pintype "output"))
    )
    (net (code "43") (name "FIRQ") (class "Default")
      (node (ref "R7") (pin "1") (pinfunction "1_1") (pintype "passive"))
      (node (ref "U14") (pin "2") (pinfunction "~{IRQ}_2") (pintype "passive"))
      (node (ref "U4") (pin "4") (pinfunction "~{FIRQ}_4") (pintype "passive"))
    )
    (net (code "44") (name "GND") (class "Default")
      (node (ref "C10") (pin "2") (pinfunction "2_2") (pintype "passive"))
      (node (ref "C100") (pin "-") (pinfunction "-_-") (pintype "passive"))
      (node (ref "C103") (pin "-") (pinfunction "-_-") (pintype "passive"))
      (node (ref "C104") (pin "1") (pinfunction "1_1") (pintype "passive"))
      (node (ref "C105") (pin "1") (pinfunction "1_1") (pintype "passive"))
      (node (ref "C106") (pin "2") (pinfunction "2_2") (pintype "passive"))
      (node (ref "C107") (pin "2") (pinfunction "2_2") (pintype "passive"))
      (node (ref "C11") (pin "2") (pinfunction "2_2") (pintype "passive"))
      (node (ref "C12") (pin "2") (pinfunction "2_2") (pintype "passive"))
      (node (ref "C13") (pin "2") (pinfunction "2_2") (pintype "passive"))
      (node (ref "C14") (pin "2") (pinfunction "2_2") (pintype "passive"))
      (node (ref "C15") (pin "2") (pinfunction "2_2") (pintype "passive"))
      (node (ref "C16") (pin "2") (pinfunction "2_2") (pintype "passive"))
      (node (ref "C17") (pin "2") (pinfunction "2_2") (pintype "passive"))
      (node (ref "C18") (pin "2") (pinfunction "2_2") (pintype "passive"))
      (node (ref "C19") (pin "2") (pinfunction "2_2") (pintype "passive"))
      (node (ref "C2") (pin "2") (pinfunction "2_2") (pintype "passive"))
      (node (ref "C20") (pin "2") (pinfunction "2_2") (pintype "passive"))
      (node (ref "C21") (pin "2") (pinfunction "2_2") (pintype "passive"))
      (node (ref "C22") (pin "2") (pinfunction "2_2") (pintype "passive"))
      (node (ref "C23") (pin "2") (pinfunction "2_2") (pintype "passive"))
      (node (ref "C24") (pin "2") (pinfunction "2_2") (pintype "passive"))
      (node (ref "C25") (pin "2") (pinfunction "2_2") (pintype "passive"))
      (node (ref "C26") (pin "2") (pinfunction "2_2") (pintype "passive"))
      (node (ref "C28") (pin "2") (pinfunction "2_2") (pintype "passive"))
      (node (ref "C3") (pin "2") (pinfunction "2_2") (pintype "passive"))
      (node (ref "C35") (pin "2") (pinfunction "2_2") (pintype "passive"))
      (node (ref "C36") (pin "2") (pinfunction "2_2") (pintype "passive"))
      (node (ref "C37") (pin "2") (pinfunction "2_2") (pintype "passive"))
      (node (ref "C38") (pin "2") (pinfunction "2_2") (pintype "passive"))
      (node (ref "C39") (pin "2") (pinfunction "2_2") (pintype "passive"))
      (node (ref "C4") (pin "2") (pinfunction "2_2") (pintype "passive"))
      (node (ref "C40") (pin "2") (pinfunction "2_2") (pintype "passive"))
      (node (ref "C41") (pin "2") (pinfunction "2_2") (pintype "passive"))
      (node (ref "C42") (pin "2") (pinfunction "2_2") (pintype "passive"))
      (node (ref "C43") (pin "2") (pinfunction "2_2") (pintype "passive"))
      (node (ref "C44") (pin "2") (pinfunction "2_2") (pintype "passive"))
      (node (ref "C45") (pin "2") (pinfunction "2_2") (pintype "passive"))
      (node (ref "C49") (pin "2") (pinfunction "2_2") (pintype "passive"))
      (node (ref "C5") (pin "2") (pinfunction "2_2") (pintype "passive"))
      (node (ref "C6") (pin "2") (pinfunction "2_2") (pintype "passive"))
      (node (ref "C7") (pin "2") (pinfunction "2_2") (pintype "passive"))
      (node (ref "C70") (pin "-") (pinfunction "-_-") (pintype "passive"))
      (node (ref "C72") (pin "2") (pinfunction "2_2") (pintype "passive"))
      (node (ref "C74") (pin "2") (pinfunction "2_2") (pintype "passive"))
      (node (ref "C8") (pin "2") (pinfunction "2_2") (pintype "passive"))
      (node (ref "C9") (pin "2") (pinfunction "2_2") (pintype "passive"))
      (node (ref "C99") (pin "2") (pinfunction "2_2") (pintype "passive"))
      (node (ref "MTG1") (pin "P1") (pinfunction "P$1_P1") (pintype "bidirectional"))
      (node (ref "MTG2") (pin "P1") (pinfunction "P$1_P1") (pintype "bidirectional"))
      (node (ref "MTG3") (pin "P1") (pinfunction "P$1_P1") (pintype "bidirectional"))
      (node (ref "MTG4") (pin "P1") (pinfunction "P$1_P1") (pintype "bidirectional"))
      (node (ref "P1") (pin "1") (pinfunction "1_1") (pintype "passive"))
      (node (ref "P4") (pin "1") (pinfunction "1_1") (pintype "passive"))
      (node (ref "P6") (pin "2") (pinfunction "2_2") (pintype "passive"))
      (node (ref "Q1") (pin "2") (pinfunction "E_2") (pintype "passive"))
      (node (ref "R4") (pin "2") (pinfunction "2_2") (pintype "passive"))
      (node (ref "R83") (pin "1") (pinfunction "1_1") (pintype "passive"))
      (node (ref "U1") (pin "1") (pinfunction "VSS_1") (pintype "passive"))
      (node (ref "U10") (pin "4") (pinfunction "EN_4") (pintype "bidirectional"))
      (node (ref "U10") (pin "8") (pinfunction "GND_8") (pintype "power_in"))
      (node (ref "U11") (pin "4") (pinfunction "EN_4") (pintype "bidirectional"))
      (node (ref "U11") (pin "8") (pinfunction "GND_8") (pintype "power_in"))
      (node (ref "U12") (pin "16") (pinfunction "VSS_16") (pintype "passive"))
      (node (ref "U12") (pin "22") (pinfunction "~{CS}_22") (pintype "passive"))
      (node (ref "U13") (pin "16") (pinfunction "VSS_16") (pintype "passive"))
      (node (ref "U13") (pin "22") (pinfunction "~{CS}_22") (pintype "passive"))
      (node (ref "U14") (pin "1") (pinfunction "VSS-1_1") (pintype "passive"))
      (node (ref "U14") (pin "11") (pinfunction "VSS-11_11") (pintype "passive"))
      (node (ref "U15") (pin "3") (pinfunction "GND_3") (pintype "power_in"))
      (node (ref "U16") (pin "10") (pinfunction "GND_10") (pintype "power_in"))
      (node (ref "U17") (pin "8") (pinfunction "GND_8") (pintype "power_in"))
      (node (ref "U18") (pin "10") (pinfunction "VSS_10") (pintype "passive"))
      (node (ref "U19") (pin "7") (pinfunction "GND_7") (pintype "power_in"))
      (node (ref "U2") (pin "14") (pinfunction "VSS_14") (pintype "power_in"))
      (node (ref "U20") (pin "13") (pinfunction "B_13") (pintype "input"))
      (node (ref "U20") (pin "8") (pinfunction "GND_8") (pintype "power_in"))
      (node (ref "U21") (pin "11") (pinfunction "I_11") (pintype "input"))
      (node (ref "U21") (pin "13") (pinfunction "I_13") (pintype "input"))
      (node (ref "U21") (pin "3") (pinfunction "I_3") (pintype "input"))
      (node (ref "U21") (pin "7") (pinfunction "GND_7") (pintype "power_in"))
      (node (ref "U22") (pin "7") (pinfunction "GND_7") (pintype "power_in"))
      (node (ref "U23") (pin "7") (pinfunction "GND_7") (pintype "power_in"))
      (node (ref "U24") (pin "8") (pinfunction "GND_8") (pintype "power_in"))
      (node (ref "U25") (pin "8") (pinfunction "GND_8") (pintype "power_in"))
      (node (ref "U26") (pin "7") (pinfunction "GND_7") (pintype "power_in"))
      (node (ref "U28") (pin "3") (pinfunction "VSS_3") (pintype "passive"))
      (node (ref "U3") (pin "16") (pinfunction "VSS_16") (pintype "passive"))
      (node (ref "U3") (pin "22") (pinfunction "~{CS}_22") (pintype "passive"))
      (node (ref "U4") (pin "1") (pinfunction "VSS_1") (pintype "passive"))
      (node (ref "U4") (pin "39") (pinfunction "TSC_39") (pintype "passive"))
      (node (ref "U5") (pin "10") (pinfunction "GND_10") (pintype "power_in"))
      (node (ref "U6") (pin "4") (pinfunction "EN_4") (pintype "bidirectional"))
      (node (ref "U6") (pin "8") (pinfunction "GND_8") (pintype "power_in"))
      (node (ref "U7") (pin "4") (pinfunction "EN_4") (pintype "bidirectional"))
      (node (ref "U7") (pin "8") (pinfunction "GND_8") (pintype "power_in"))
      (node (ref "U8") (pin "8") (pinfunction "GND_8") (pintype "power_in"))
      (node (ref "U9") (pin "7") (pinfunction "GND_7") (pintype "power_in"))
      (node (ref "W8") (pin "1") (pinfunction "1_1") (pintype "passive"))
      (node (ref "Y2") (pin "2") (pinfunction "GND_2") (pintype "bidirectional"))
    )
    (net (code "45") (name "IRQ") (class "Default")
      (node (ref "R5") (pin "1") (pinfunction "1_1") (pintype "passive"))
      (node (ref "U23") (pin "9") (pinfunction "Q_9") (pintype "output"))
      (node (ref "U24") (pin "15") (pinfunction "IND_15") (pintype "input"))
      (node (ref "U4") (pin "3") (pinfunction "~{IRQ}_3") (pintype "passive"))
    )
    (net (code "46") (name "MIX-OUT") (class "Default")
      (node (ref "C68") (pin "-") (pinfunction "-_-") (pintype "passive"))
      (node (ref "U30") (pin "1") (pinfunction "VIN_1") (pintype "bidirectional"))
    )
    (net (code "47") (name "Net-(C47-Pad1)") (class "Default")
      (node (ref "C47") (pin "1") (pinfunction "1_1") (pintype "passive"))
      (node (ref "Y1") (pin "2") (pinfunction "2_2") (pintype "passive"))
    )
    (net (code "48") (name "Net-(C52-Pad2)") (class "Default")
      (node (ref "C52") (pin "2") (pinfunction "2_2") (pintype "passive"))
      (node (ref "R38") (pin "2") (pinfunction "2_2") (pintype "passive"))
      (node (ref "R39") (pin "1") (pinfunction "1_1") (pintype "passive"))
    )
    (net (code "49") (name "Net-(C54-Pad1)") (class "Default")
      (node (ref "C54") (pin "1") (pinfunction "1_1") (pintype "passive"))
      (node (ref "R44") (pin "1") (pinfunction "1_1") (pintype "passive"))
      (node (ref "R45") (pin "2") (pinfunction "2_2") (pintype "passive"))
      (node (ref "R46") (pin "2") (pinfunction "2_2") (pintype "passive"))
    )
    (net (code "50") (name "Net-(C58-Pad2)") (class "Default")
      (node (ref "C58") (pin "2") (pinfunction "2_2") (pintype "passive"))
      (node (ref "R35") (pin "1") (pinfunction "1_1") (pintype "passive"))
      (node (ref "R36") (pin "2") (pinfunction "2_2") (pintype "passive"))
    )
    (net (code "51") (name "Net-(C61-Pad1)") (class "Default")
      (node (ref "C61") (pin "1") (pinfunction "1_1") (pintype "passive"))
      (node (ref "R40") (pin "1") (pinfunction "1_1") (pintype "passive"))
      (node (ref "R51") (pin "2") (pinfunction "2_2") (pintype "passive"))
      (node (ref "R52") (pin "2") (pinfunction "2_2") (pintype "passive"))
    )
    (net (code "52") (name "Net-(C69-Pad1)") (class "Default")
      (node (ref "C69") (pin "1") (pinfunction "1_1") (pintype "passive"))
      (node (ref "R62") (pin "1") (pinfunction "1_1") (pintype "passive"))
      (node (ref "R63") (pin "2") (pinfunction "2_2") (pintype "passive"))
      (node (ref "R64") (pin "2") (pinfunction "2_2") (pintype "passive"))
    )
    (net (code "53") (name "Net-(C74-Pad1)") (class "Default")
      (node (ref "C74") (pin "1") (pinfunction "1_1") (pintype "passive"))
      (node (ref "L1") (pin "2") (pinfunction "2_2") (pintype "passive"))
      (node (ref "P6") (pin "1") (pinfunction "1_1") (pintype "passive"))
    )
    (net (code "54") (name "Net-(C75-Pad-)") (class "Default")
      (node (ref "C75") (pin "-") (pinfunction "-_-") (pintype "passive"))
      (node (ref "P3") (pin "3") (pinfunction "3_3") (pintype "passive"))
    )
    (net (code "55") (name "Net-(C81-Pad+)") (class "Default")
      (node (ref "C81") (pin "+") (pinfunction "+_+") (pintype "passive"))
      (node (ref "R70") (pin "1") (pinfunction "1_1") (pintype "passive"))
      (node (ref "R71") (pin "2") (pinfunction "2_2") (pintype "passive"))
    )
    (net (code "56") (name "Net-(C88-Pad1)") (class "Default")
      (node (ref "C88") (pin "1") (pinfunction "1_1") (pintype "passive"))
      (node (ref "L2") (pin "1") (pinfunction "1_1") (pintype "passive"))
      (node (ref "P6") (pin "5") (pinfunction "5_5") (pintype "passive"))
      (node (ref "P6") (pin "6") (pinfunction "6_6") (pintype "passive"))
    )
    (net (code "57") (name "Net-(CR1-PadC)") (class "Default")
      (node (ref "CR1") (pin "C") (pinfunction "C_C") (pintype "passive"))
      (node (ref "R30") (pin "1") (pinfunction "1_1") (pintype "passive"))
    )
    (net (code "58") (name "Net-(CR2-C)") (class "Default")
      (node (ref "C73") (pin "+") (pinfunction "+_+") (pintype "passive"))
      (node (ref "CR2") (pin "3") (pinfunction "C_3") (pintype "passive"))
      (node (ref "R54") (pin "2") (pinfunction "2_2") (pintype "passive"))
      (node (ref "U32") (pin "10") (pinfunction "+IN_10") (pintype "input"))
      (node (ref "U33") (pin "10") (pinfunction "+IN_10") (pintype "input"))
      (node (ref "U33") (pin "12") (pinfunction "+IN_12") (pintype "input"))
      (node (ref "U33") (pin "3") (pinfunction "+IN_3") (pintype "input"))
      (node (ref "U33") (pin "5") (pinfunction "+IN_5") (pintype "input"))
    )
    (net (code "59") (name "Net-(P1-Pad13)") (class "Default")
      (node (ref "P1") (pin "13") (pinfunction "13_13") (pintype "passive"))
      (node (ref "R96") (pin "2") (pinfunction "2_2") (pintype "passive"))
    )
    (net (code "60") (name "Net-(P1-Pad16)") (class "Default")
      (node (ref "P1") (pin "16") (pinfunction "16_16") (pintype "passive"))
      (node (ref "R95") (pin "2") (pinfunction "2_2") (pintype "passive"))
    )
    (net (code "61") (name "Net-(P1-Pad17)") (class "Default")
      (node (ref "P1") (pin "17") (pinfunction "17_17") (pintype "passive"))
      (node (ref "R93") (pin "2") (pinfunction "2_2") (pintype "passive"))
    )
    (net (code "62") (name "Net-(P1-Pad18)") (class "Default")
      (node (ref "P1") (pin "18") (pinfunction "18_18") (pintype "passive"))
      (node (ref "R94") (pin "2") (pinfunction "2_2") (pintype "passive"))
    )
    (net (code "63") (name "Net-(P2-Pad3)") (class "Default")
      (node (ref "P2") (pin "3") (pinfunction "3_3") (pintype "passive"))
      (node (ref "R53") (pin "2") (pinfunction "2_2") (pintype "passive"))
    )
    (net (code "64") (name "Net-(P5-Pad2)") (class "Default")
      (node (ref "P5") (pin "2") (pinfunction "2_2") (pintype "passive"))
      (node (ref "R87") (pin "2") (pinfunction "2_2") (pintype "passive"))
    )
    (net (code "65") (name "Net-(Q1-B)") (class "Default")
      (node (ref "C62") (pin "2") (pinfunction "2_2") (pintype "passive"))
      (node (ref "Q1") (pin "1") (pinfunction "B_1") (pintype "passive"))
      (node (ref "R28") (pin "2") (pinfunction "2_2") (pintype "passive"))
    )
    (net (code "66") (name "Net-(Q1-C)") (class "Default")
      (node (ref "Q1") (pin "3") (pinfunction "C_3") (pintype "passive"))
      (node (ref "R27") (pin "1") (pinfunction "1_1") (pintype "passive"))
      (node (ref "U4") (pin "34") (pinfunction "E_34") (pintype "passive"))
    )
    (net (code "67") (name "Net-(R8-Pad1)") (class "Default")
      (node (ref "R8") (pin "1") (pinfunction "1_1") (pintype "passive"))
      (node (ref "W1") (pin "1") (pinfunction "1_1") (pintype "passive"))
    )
    (net (code "68") (name "Net-(U1-DAO)") (class "Default")
      (node (ref "C46") (pin "-") (pinfunction "-_-") (pintype "passive"))
      (node (ref "U1") (pin "36") (pinfunction "DAO_36") (pintype "passive"))
    )
    (net (code "69") (name "Net-(U1-VCC)") (class "Default")
      (node (ref "C103") (pin "+") (pinfunction "+_+") (pintype "passive"))
      (node (ref "C99") (pin "1") (pinfunction "1_1") (pintype "passive"))
      (node (ref "R89") (pin "1") (pinfunction "1_1") (pintype "passive"))
      (node (ref "U1") (pin "17") (pinfunction "VCC_17") (pintype "passive"))
    )
    (net (code "70") (name "Net-(U2-CS2)") (class "Default")
      (node (ref "R1") (pin "1") (pinfunction "1_1") (pintype "passive"))
      (node (ref "U2") (pin "26") (pinfunction "CS2_26") (pintype "input"))
    )
    (net (code "71") (name "Net-(U2-~{CS1})") (class "Default")
      (node (ref "U2") (pin "20") (pinfunction "~{CS1}_20") (pintype "input"))
      (node (ref "U20") (pin "12") (pinfunction "Y0_12") (pintype "output"))
    )
    (net (code "72") (name "Net-(U3-A14)") (class "Default")
      (node (ref "U3") (pin "29") (pinfunction "A14_29") (pintype "passive"))
      (node (ref "W5") (pin "2") (pinfunction "2_2") (pintype "passive"))
      (node (ref "W6") (pin "2") (pinfunction "2_2") (pintype "passive"))
    )
    (net (code "73") (name "Net-(U3-A17)") (class "Default")
      (node (ref "U3") (pin "30") (pinfunction "A17_30") (pintype "passive"))
      (node (ref "W1") (pin "2") (pinfunction "2_2") (pintype "passive"))
      (node (ref "W2") (pin "2") (pinfunction "2_2") (pintype "passive"))
    )
    (net (code "74") (name "Net-(U3-A18)") (class "Default")
      (node (ref "U3") (pin "31") (pinfunction "A18_31") (pintype "passive"))
      (node (ref "W3") (pin "2") (pinfunction "2_2") (pintype "passive"))
      (node (ref "W4") (pin "2") (pinfunction "2_2") (pintype "passive"))
    )
    (net (code "75") (name "Net-(U4-~{HALT})") (class "Default")
      (node (ref "R6") (pin "1") (pinfunction "1_1") (pintype "passive"))
      (node (ref "U4") (pin "40") (pinfunction "~{HALT}_40") (pintype "passive"))
    )
    (net (code "76") (name "Net-(U4-~{NMI})") (class "Default")
      (node (ref "R2") (pin "1") (pinfunction "1_1") (pintype "passive"))
      (node (ref "U4") (pin "2") (pinfunction "~{NMI}_2") (pintype "passive"))
    )
    (net (code "77") (name "Net-(U5A-1Q)") (class "Default")
      (node (ref "U5") (pin "2") (pinfunction "1Q_2") (pintype "tri_state"))
      (node (ref "U7") (pin "1") (pinfunction "INA_1") (pintype "input"))
    )
    (net (code "78") (name "Net-(U5A-2Q)") (class "Default")
      (node (ref "U5") (pin "5") (pinfunction "2Q_5") (pintype "tri_state"))
      (node (ref "U7") (pin "7") (pinfunction "INB_7") (pintype "input"))
    )
    (net (code "79") (name "Net-(U5A-3Q)") (class "Default")
      (node (ref "U5") (pin "6") (pinfunction "3Q_6") (pintype "tri_state"))
      (node (ref "U7") (pin "9") (pinfunction "INC_9") (pintype "input"))
    )
    (net (code "80") (name "Net-(U5A-4Q)") (class "Default")
      (node (ref "U5") (pin "9") (pinfunction "4Q_9") (pintype "tri_state"))
      (node (ref "U7") (pin "15") (pinfunction "IND_15") (pintype "input"))
    )
    (net (code "81") (name "Net-(U6-INA)") (class "Default")
      (node (ref "R11") (pin "1") (pinfunction "1_1") (pintype "passive"))
      (node (ref "U6") (pin "2") (pinfunction "INA_2") (pintype "bidirectional"))
      (node (ref "U7") (pin "2") (pinfunction "OUTA_2") (pintype "bidirectional"))
    )
    (net (code "82") (name "Net-(U6-INB)") (class "Default")
      (node (ref "R13") (pin "1") (pinfunction "1_1") (pintype "passive"))
      (node (ref "U6") (pin "6") (pinfunction "INB_6") (pintype "bidirectional"))
      (node (ref "U7") (pin "6") (pinfunction "OUTB_6") (pintype "bidirectional"))
    )
    (net (code "83") (name "Net-(U6-INC)") (class "Default")
      (node (ref "R14") (pin "1") (pinfunction "1_1") (pintype "passive"))
      (node (ref "U6") (pin "10") (pinfunction "INC_10") (pintype "bidirectional"))
      (node (ref "U7") (pin "10") (pinfunction "OUTC_10") (pintype "bidirectional"))
    )
    (net (code "84") (name "Net-(U6-IND)") (class "Default")
      (node (ref "R12") (pin "1") (pinfunction "1_1") (pintype "passive"))
      (node (ref "U6") (pin "14") (pinfunction "IND_14") (pintype "bidirectional"))
      (node (ref "U7") (pin "14") (pinfunction "OUTD_14") (pintype "bidirectional"))
    )
    (net (code "85") (name "Net-(U9A-D)") (class "Default")
      (node (ref "U9") (pin "2") (pinfunction "D_2") (pintype "input"))
      (node (ref "U9") (pin "6") (pinfunction "~{Q}_6") (pintype "output"))
    )
    (net (code "86") (name "Net-(U10-INA)") (class "Default")
      (node (ref "R15") (pin "1") (pinfunction "1_1") (pintype "passive"))
      (node (ref "U10") (pin "2") (pinfunction "INA_2") (pintype "bidirectional"))
      (node (ref "U11") (pin "2") (pinfunction "OUTA_2") (pintype "bidirectional"))
    )
    (net (code "87") (name "Net-(U10-INB)") (class "Default")
      (node (ref "R16") (pin "1") (pinfunction "1_1") (pintype "passive"))
      (node (ref "U10") (pin "6") (pinfunction "INB_6") (pintype "bidirectional"))
      (node (ref "U11") (pin "6") (pinfunction "OUTB_6") (pintype "bidirectional"))
    )
    (net (code "88") (name "Net-(U10-INC)") (class "Default")
      (node (ref "R17") (pin "1") (pinfunction "1_1") (pintype "passive"))
      (node (ref "U10") (pin "10") (pinfunction "INC_10") (pintype "bidirectional"))
      (node (ref "U11") (pin "10") (pinfunction "OUTC_10") (pintype "bidirectional"))
    )
    (net (code "89") (name "Net-(U10-IND)") (class "Default")
      (node (ref "R18") (pin "1") (pinfunction "1_1") (pintype "passive"))
      (node (ref "U10") (pin "14") (pinfunction "IND_14") (pintype "bidirectional"))
      (node (ref "U11") (pin "14") (pinfunction "OUTD_14") (pintype "bidirectional"))
    )
    (net (code "90") (name "Net-(U10-~{INA})") (class "Default")
      (node (ref "R82") (pin "1") (pinfunction "1_1") (pintype "passive"))
      (node (ref "R83") (pin "2") (pinfunction "2_2") (pintype "passive"))
      (node (ref "U10") (pin "1") (pinfunction "~{INA}_1") (pintype "bidirectional"))
      (node (ref "U10") (pin "15") (pinfunction "~{IND}_15") (pintype "bidirectional"))
      (node (ref "U10") (pin "7") (pinfunction "~{INB}_7") (pintype "bidirectional"))
      (node (ref "U10") (pin "9") (pinfunction "~{INC}_9") (pintype "bidirectional"))
      (node (ref "U25") (pin "1") (pinfunction "~{INA}_1") (pintype "bidirectional"))
      (node (ref "U25") (pin "15") (pinfunction "~{IND}_15") (pintype "bidirectional"))
      (node (ref "U25") (pin "7") (pinfunction "~{INB}_7") (pintype "bidirectional"))
      (node (ref "U25") (pin "9") (pinfunction "~{INC}_9") (pintype "bidirectional"))
      (node (ref "U6") (pin "1") (pinfunction "~{INA}_1") (pintype "bidirectional"))
      (node (ref "U6") (pin "15") (pinfunction "~{IND}_15") (pintype "bidirectional"))
      (node (ref "U6") (pin "7") (pinfunction "~{INB}_7") (pintype "bidirectional"))
      (node (ref "U6") (pin "9") (pinfunction "~{INC}_9") (pintype "bidirectional"))
    )
    (net (code "91") (name "Net-(U11-INA)") (class "Default")
      (node (ref "U11") (pin "1") (pinfunction "INA_1") (pintype "input"))
      (node (ref "U5") (pin "12") (pinfunction "5Q_12") (pintype "tri_state"))
    )
    (net (code "92") (name "Net-(U11-INB)") (class "Default")
      (node (ref "U11") (pin "7") (pinfunction "INB_7") (pintype "input"))
      (node (ref "U5") (pin "15") (pinfunction "6Q_15") (pintype "tri_state"))
    )
    (net (code "93") (name "Net-(U11-INC)") (class "Default")
      (node (ref "U11") (pin "9") (pinfunction "INC_9") (pintype "input"))
      (node (ref "U5") (pin "16") (pinfunction "7Q_16") (pintype "tri_state"))
    )
    (net (code "94") (name "Net-(U11-IND)") (class "Default")
      (node (ref "U11") (pin "15") (pinfunction "IND_15") (pintype "input"))
      (node (ref "U5") (pin "19") (pinfunction "8Q_19") (pintype "tri_state"))
    )
    (net (code "95") (name "Net-(U12-~{OE})") (class "Default")
      (node (ref "U12") (pin "24") (pinfunction "~{OE}_24") (pintype "passive"))
      (node (ref "U19") (pin "8") (pinfunction "O_8") (pintype "output"))
      (node (ref "U26") (pin "11") (pinfunction "I_11") (pintype "input"))
    )
    (net (code "96") (name "Net-(U13-~{OE})") (class "Default")
      (node (ref "U13") (pin "24") (pinfunction "~{OE}_24") (pintype "passive"))
      (node (ref "U26") (pin "10") (pinfunction "O_10") (pintype "output"))
    )
    (net (code "97") (name "Net-(U14-CLK)") (class "Default")
      (node (ref "U14") (pin "23") (pinfunction "CLK_23") (pintype "passive"))
      (node (ref "U28") (pin "2") (pinfunction "CLK_2") (pintype "passive"))
    )
    (net (code "98") (name "Net-(U14-OSC)") (class "Default")
      (node (ref "U14") (pin "24") (pinfunction "OSC_24") (pintype "passive"))
      (node (ref "W7") (pin "1") (pinfunction "1_1") (pintype "passive"))
    )
    (net (code "99") (name "Net-(U14-SH1)") (class "Default")
      (node (ref "U14") (pin "20") (pinfunction "SH1_20") (pintype "passive"))
      (node (ref "U28") (pin "6") (pinfunction "SAM1_6") (pintype "passive"))
    )
    (net (code "100") (name "Net-(U14-SH2)") (class "Default")
      (node (ref "U14") (pin "19") (pinfunction "SH2_19") (pintype "passive"))
      (node (ref "U28") (pin "5") (pinfunction "SAM2_5") (pintype "passive"))
    )
    (net (code "101") (name "Net-(U14-SO)") (class "Default")
      (node (ref "U14") (pin "21") (pinfunction "SO_21") (pintype "passive"))
      (node (ref "U28") (pin "4") (pinfunction "SO_4") (pintype "passive"))
    )
    (net (code "102") (name "Net-(U15-OUT1)") (class "Default")
      (node (ref "C63") (pin "+") (pinfunction "+_+") (pintype "passive"))
      (node (ref "R68") (pin "2") (pinfunction "2_2") (pintype "passive"))
      (node (ref "R69") (pin "1") (pinfunction "1_1") (pintype "passive"))
      (node (ref "U15") (pin "1") (pinfunction "OUT1_1") (pintype "passive"))
    )
    (net (code "103") (name "Net-(U15-VREF)") (class "Default")
      (node (ref "C98") (pin "1") (pinfunction "1_1") (pintype "passive"))
      (node (ref "U15") (pin "15") (pinfunction "VREF_15") (pintype "input"))
      (node (ref "U29") (pin "12") (pinfunction "+IN_12") (pintype "input"))
    )
    (net (code "104") (name "Net-(U16A-1Q)") (class "Default")
      (node (ref "R24") (pin "1") (pinfunction "1_1") (pintype "passive"))
      (node (ref "U16") (pin "2") (pinfunction "1Q_2") (pintype "tri_state"))
      (node (ref "U3") (pin "3") (pinfunction "A15_3") (pintype "passive"))
    )
    (net (code "105") (name "Net-(U16A-2Q)") (class "Default")
      (node (ref "R23") (pin "1") (pinfunction "1_1") (pintype "passive"))
      (node (ref "U16") (pin "5") (pinfunction "2Q_5") (pintype "tri_state"))
      (node (ref "U3") (pin "2") (pinfunction "A16_2") (pintype "passive"))
    )
    (net (code "106") (name "Net-(U16A-3Q)") (class "Default")
      (node (ref "R22") (pin "1") (pinfunction "1_1") (pintype "passive"))
      (node (ref "U16") (pin "6") (pinfunction "3Q_6") (pintype "tri_state"))
      (node (ref "W2") (pin "1") (pinfunction "1_1") (pintype "passive"))
    )
    (net (code "107") (name "Net-(U16A-4Q)") (class "Default")
      (node (ref "R26") (pin "1") (pinfunction "1_1") (pintype "passive"))
      (node (ref "U16") (pin "9") (pinfunction "4Q_9") (pintype "tri_state"))
      (node (ref "W3") (pin "1") (pinfunction "1_1") (pintype "passive"))
    )
    (net (code "108") (name "Net-(U16A-CLK)") (class "Default")
      (node (ref "U16") (pin "11") (pinfunction "CLK_11") (pintype "input"))
      (node (ref "U26") (pin "8") (pinfunction "O_8") (pintype "output"))
    )
    (net (code "109") (name "Net-(U16A-OC)") (class "Default")
      (node (ref "U16") (pin "1") (pinfunction "OC_1") (pintype "input"))
      (node (ref "U8") (pin "15") (pinfunction "Y0_15") (pintype "output"))
    )
    (net (code "110") (name "Net-(U18-7-IN)") (class "Default")
      (node (ref "P4") (pin "4") (pinfunction "4_4") (pintype "passive"))
      (node (ref "R91") (pin "1") (pinfunction "1_1") (pintype "passive"))
      (node (ref "U18") (pin "7") (pinfunction "7-IN_7") (pintype "passive"))
    )
    (net (code "111") (name "Net-(U18-11-IN)") (class "Default")
      (node (ref "U18") (pin "11") (pinfunction "11-IN_11") (pintype "passive"))
      (node (ref "U19") (pin "6") (pinfunction "O_6") (pintype "output"))
      (node (ref "U3") (pin "24") (pinfunction "~{OE}_24") (pintype "passive"))
    )
    (net (code "112") (name "Net-(U19A-I0)") (class "Default")
      (node (ref "U19") (pin "1") (pinfunction "I0_1") (pintype "input"))
      (node (ref "U21") (pin "2") (pinfunction "O_2") (pintype "output"))
    )
    (net (code "113") (name "Net-(U19B-I0)") (class "Default")
      (node (ref "U19") (pin "3") (pinfunction "I0_3") (pintype "input"))
      (node (ref "U20") (pin "5") (pinfunction "Y1_5") (pintype "output"))
    )
    (net (code "114") (name "Net-(U19B-I1)") (class "Default")
      (node (ref "U19") (pin "4") (pinfunction "I1_4") (pintype "input"))
      (node (ref "U20") (pin "6") (pinfunction "Y2_6") (pintype "output"))
    )
    (net (code "115") (name "Net-(U19B-I2)") (class "Default")
      (node (ref "U19") (pin "5") (pinfunction "I2_5") (pintype "input"))
      (node (ref "U20") (pin "7") (pinfunction "Y3_7") (pintype "output"))
      (node (ref "U26") (pin "9") (pinfunction "I_9") (pintype "input"))
    )
    (net (code "116") (name "Net-(U19C-I2)") (class "Default")
      (node (ref "U19") (pin "11") (pinfunction "I2_11") (pintype "input"))
      (node (ref "U26") (pin "12") (pinfunction "O_12") (pintype "output"))
    )
    (net (code "117") (name "Net-(U20A-Y0)") (class "Default")
      (node (ref "U20") (pin "15") (pinfunction "G_15") (pintype "input"))
      (node (ref "U20") (pin "4") (pinfunction "Y0_4") (pintype "output"))
    )
    (net (code "118") (name "Net-(U20B-Y1)") (class "Default")
      (node (ref "U20") (pin "11") (pinfunction "Y1_11") (pintype "output"))
      (node (ref "U8") (pin "4") (pinfunction "G2A_4") (pintype "input"))
      (node (ref "U8") (pin "5") (pinfunction "G2B_5") (pintype "input"))
    )
    (net (code "119") (name "Net-(U21C-I)") (class "Default")
      (node (ref "C100") (pin "+") (pinfunction "+_+") (pintype "passive"))
      (node (ref "CR1") (pin "A") (pinfunction "A_A") (pintype "passive"))
      (node (ref "R29") (pin "1") (pinfunction "1_1") (pintype "passive"))
      (node (ref "U21") (pin "9") (pinfunction "I_9") (pintype "input"))
    )
    (net (code "120") (name "Net-(U21C-O)") (class "Default")
      (node (ref "U21") (pin "1") (pinfunction "I_1") (pintype "input"))
      (node (ref "U21") (pin "8") (pinfunction "O_8") (pintype "output"))
    )
    (net (code "121") (name "Net-(U21F-I)") (class "Default")
      (node (ref "U21") (pin "5") (pinfunction "I_5") (pintype "input"))
      (node (ref "Y2") (pin "3") (pinfunction "OUT_3") (pintype "bidirectional"))
    )
    (net (code "122") (name "Net-(U21F-O)") (class "Default")
      (node (ref "U21") (pin "6") (pinfunction "O_6") (pintype "output"))
      (node (ref "U22") (pin "3") (pinfunction "CLK_3") (pintype "input"))
      (node (ref "U23") (pin "3") (pinfunction "CLK_3") (pintype "input"))
    )
    (net (code "123") (name "Net-(U22A-D)") (class "Default")
      (node (ref "U22") (pin "2") (pinfunction "D_2") (pintype "input"))
      (node (ref "U23") (pin "5") (pinfunction "Q_5") (pintype "output"))
      (node (ref "U4") (pin "35") (pinfunction "Q_35") (pintype "passive"))
    )
    (net (code "124") (name "Net-(U22A-PRE)") (class "Default")
      (node (ref "R10") (pin "1") (pinfunction "1_1") (pintype "passive"))
      (node (ref "U22") (pin "10") (pinfunction "PRE_10") (pintype "input"))
      (node (ref "U22") (pin "11") (pinfunction "CLK_11") (pintype "input"))
      (node (ref "U22") (pin "12") (pinfunction "D_12") (pintype "input"))
      (node (ref "U22") (pin "4") (pinfunction "PRE_4") (pintype "input"))
      (node (ref "U23") (pin "4") (pinfunction "PRE_4") (pintype "input"))
      (node (ref "U9") (pin "4") (pinfunction "PRE_4") (pintype "input"))
    )
    (net (code "125") (name "Net-(U22A-Q)") (class "Default")
      (node (ref "U22") (pin "5") (pinfunction "Q_5") (pintype "output"))
      (node (ref "U9") (pin "3") (pinfunction "CLK_3") (pintype "input"))
    )
    (net (code "126") (name "Net-(U23B-CLK)") (class "Default")
      (node (ref "U23") (pin "11") (pinfunction "CLK_11") (pintype "input"))
      (node (ref "U25") (pin "13") (pinfunction "OUTD_13") (pintype "bidirectional"))
    )
    (net (code "127") (name "Net-(U23B-D)") (class "Default")
      (node (ref "R4") (pin "1") (pinfunction "1_1") (pintype "passive"))
      (node (ref "U23") (pin "12") (pinfunction "D_12") (pintype "input"))
      (node (ref "U24") (pin "12") (pinfunction "~{EN}_12") (pintype "bidirectional"))
      (node (ref "U25") (pin "12") (pinfunction "~{EN}_12") (pintype "bidirectional"))
      (node (ref "U5") (pin "1") (pinfunction "OC_1") (pintype "input"))
    )
    (net (code "128") (name "Net-(U24-OUTA)") (class "Default")
      (node (ref "R21") (pin "1") (pinfunction "1_1") (pintype "passive"))
      (node (ref "U24") (pin "2") (pinfunction "OUTA_2") (pintype "bidirectional"))
    )
    (net (code "129") (name "Net-(U24-OUTB)") (class "Default")
      (node (ref "R20") (pin "1") (pinfunction "1_1") (pintype "passive"))
      (node (ref "U24") (pin "6") (pinfunction "OUTB_6") (pintype "bidirectional"))
    )
    (net (code "130") (name "Net-(U24-OUTD)") (class "Default")
      (node (ref "R19") (pin "1") (pinfunction "1_1") (pintype "passive"))
      (node (ref "U24") (pin "14") (pinfunction "OUTD_14") (pintype "bidirectional"))
    )
    (net (code "131") (name "Net-(U26A-I)") (class "Default")
      (node (ref "C49") (pin "1") (pinfunction "1_1") (pintype "passive"))
      (node (ref "R32") (pin "1") (pinfunction "1_1") (pintype "passive"))
      (node (ref "U26") (pin "1") (pinfunction "I_1") (pintype "input"))
      (node (ref "Y1") (pin "1") (pinfunction "1_1") (pintype "passive"))
    )
    (net (code "132") (name "Net-(U26A-O)") (class "Default")
      (node (ref "R32") (pin "2") (pinfunction "2_2") (pintype "passive"))
      (node (ref "R34") (pin "1") (pinfunction "1_1") (pintype "passive"))
      (node (ref "U26") (pin "2") (pinfunction "O_2") (pintype "output"))
      (node (ref "U26") (pin "3") (pinfunction "I_3") (pintype "input"))
    )
    (net (code "133") (name "Net-(U26B-O)") (class "Default")
      (node (ref "C47") (pin "2") (pinfunction "2_2") (pintype "passive"))
      (node (ref "R34") (pin "2") (pinfunction "2_2") (pintype "passive"))
      (node (ref "U26") (pin "4") (pinfunction "O_4") (pintype "output"))
      (node (ref "U26") (pin "5") (pinfunction "I_5") (pintype "input"))
    )
    (net (code "134") (name "Net-(U26C-O)") (class "Default")
      (node (ref "U26") (pin "6") (pinfunction "O_6") (pintype "output"))
      (node (ref "W7") (pin "2") (pinfunction "2_2") (pintype "passive"))
    )
    (net (code "135") (name "Net-(U28-BIAS)") (class "Default")
      (node (ref "C55") (pin "2") (pinfunction "2_2") (pintype "passive"))
      (node (ref "R41") (pin "2") (pinfunction "2_2") (pintype "passive"))
      (node (ref "U28") (pin "13") (pinfunction "BIAS_13") (pintype "passive"))
      (node (ref "U29") (pin "7") (pinfunction "OUT_7") (pintype "output"))
    )
    (net (code "136") (name "Net-(U28-BIAS+)") (class "Default")
      (node (ref "C64") (pin "+") (pinfunction "+_+") (pintype "passive"))
      (node (ref "U28") (pin "15") (pinfunction "BIAS+_15") (pintype "passive"))
      (node (ref "U29") (pin "5") (pinfunction "+IN_5") (pintype "input"))
    )
    (net (code "137") (name "Net-(U28-BIAS-)") (class "Default")
      (node (ref "C55") (pin "1") (pinfunction "1_1") (pintype "passive"))
      (node (ref "U28") (pin "14") (pinfunction "BIAS-_14") (pintype "passive"))
      (node (ref "U29") (pin "6") (pinfunction "-IN_6") (pintype "input"))
    )
    (net (code "138") (name "Net-(U28-BUFF)") (class "Default")
      (node (ref "U28") (pin "12") (pinfunction "BUFF_12") (pintype "passive"))
      (node (ref "U29") (pin "3") (pinfunction "+IN_3") (pintype "input"))
    )
    (net (code "139") (name "Net-(U28-CH1)") (class "Default")
      (node (ref "C51") (pin "1") (pinfunction "1_1") (pintype "passive"))
      (node (ref "C53") (pin "-") (pinfunction "-_-") (pintype "passive"))
      (node (ref "R37") (pin "2") (pinfunction "2_2") (pintype "passive"))
      (node (ref "U28") (pin "9") (pinfunction "CH1_9") (pintype "passive"))
    )
    (net (code "140") (name "Net-(U28-CH2)") (class "Default")
      (node (ref "C56") (pin "1") (pinfunction "1_1") (pintype "passive"))
      (node (ref "C57") (pin "-") (pinfunction "-_-") (pintype "passive"))
      (node (ref "R42") (pin "2") (pinfunction "2_2") (pintype "passive"))
      (node (ref "U28") (pin "10") (pinfunction "CH2_10") (pintype "passive"))
    )
    (net (code "141") (name "Net-(U28-COM)") (class "Default")
      (node (ref "R43") (pin "2") (pinfunction "2_2") (pintype "passive"))
      (node (ref "U28") (pin "11") (pinfunction "COM_11") (pintype "passive"))
    )
    (net (code "142") (name "Net-(U29A--IN)") (class "Default")
      (node (ref "R43") (pin "1") (pinfunction "1_1") (pintype "passive"))
      (node (ref "U29") (pin "1") (pinfunction "OUT_1") (pintype "output"))
      (node (ref "U29") (pin "2") (pinfunction "-IN_2") (pintype "input"))
    )
    (net (code "143") (name "Net-(U29C-+IN)") (class "Default")
      (node (ref "C67") (pin "+") (pinfunction "+_+") (pintype "passive"))
      (node (ref "R55") (pin "1") (pinfunction "1_1") (pintype "passive"))
      (node (ref "R60") (pin "2") (pinfunction "2_2") (pintype "passive"))
      (node (ref "U29") (pin "10") (pinfunction "+IN_10") (pintype "input"))
    )
    (net (code "144") (name "Net-(U29D--IN)") (class "Default")
      (node (ref "C67") (pin "-") (pinfunction "-_-") (pintype "passive"))
      (node (ref "R59") (pin "2") (pinfunction "2_2") (pintype "passive"))
      (node (ref "U29") (pin "13") (pinfunction "-IN_13") (pintype "input"))
      (node (ref "U29") (pin "14") (pinfunction "OUT_14") (pintype "output"))
    )
    (net (code "145") (name "Net-(U30-CNTL)") (class "Default")
      (node (ref "C66") (pin "+") (pinfunction "+_+") (pintype "passive"))
      (node (ref "C97") (pin "2") (pinfunction "2_2") (pintype "passive"))
      (node (ref "R87") (pin "1") (pinfunction "1_1") (pintype "passive"))
      (node (ref "U30") (pin "2") (pinfunction "CNTL_2") (pintype "passive"))
    )
    (net (code "146") (name "Net-(U30-ROLOFF)") (class "Default")
      (node (ref "C76") (pin "1") (pinfunction "1_1") (pintype "passive"))
      (node (ref "U30") (pin "5") (pinfunction "ROLOFF_5") (pintype "passive"))
    )
    (net (code "147") (name "Net-(U30-VO)") (class "Default")
      (node (ref "R71") (pin "1") (pinfunction "1_1") (pintype "passive"))
      (node (ref "R80") (pin "2") (pinfunction "2_2") (pintype "passive"))
      (node (ref "U30") (pin "7") (pinfunction "VO_7") (pintype "output"))
    )
    (net (code "148") (name "Net-(U31-BS-I)") (class "Default")
      (node (ref "C86") (pin "+") (pinfunction "+_+") (pintype "passive"))
      (node (ref "U31") (pin "9") (pinfunction "BS-I_9") (pintype "passive"))
    )
    (net (code "149") (name "Net-(U31-BS-M)") (class "Default")
      (node (ref "C87") (pin "+") (pinfunction "+_+") (pintype "passive"))
      (node (ref "U31") (pin "12") (pinfunction "BS-M_12") (pintype "output"))
    )
    (net (code "150") (name "Net-(U31-BYPASS)") (class "Default")
      (node (ref "C84") (pin "+") (pinfunction "+_+") (pintype "passive"))
      (node (ref "R92") (pin "2") (pinfunction "2_2") (pintype "passive"))
      (node (ref "U31") (pin "5") (pinfunction "BYPASS_5") (pintype "passive"))
    )
    (net (code "151") (name "Net-(U31-FEEDBACK)") (class "Default")
      (node (ref "C83") (pin "+") (pinfunction "+_+") (pintype "passive"))
      (node (ref "U31") (pin "4") (pinfunction "FEEDBACK_4") (pintype "passive"))
    )
    (net (code "152") (name "Net-(U31-IN)") (class "Default")
      (node (ref "C81") (pin "-") (pinfunction "-_-") (pintype "passive"))
      (node (ref "R92") (pin "1") (pinfunction "1_1") (pintype "passive"))
      (node (ref "U31") (pin "1") (pinfunction "IN_1") (pintype "passive"))
    )
    (net (code "153") (name "Net-(U31-MUTE)") (class "Default")
      (node (ref "C80") (pin "+") (pinfunction "+_+") (pintype "passive"))
      (node (ref "U31") (pin "6") (pinfunction "MUTE_6") (pintype "passive"))
    )
    (net (code "154") (name "Net-(U31-OUT(I))") (class "Default")
      (node (ref "C86") (pin "-") (pinfunction "-_-") (pintype "passive"))
      (node (ref "C90") (pin "2") (pinfunction "2_2") (pintype "passive"))
      (node (ref "C92") (pin "2") (pinfunction "2_2") (pintype "passive"))
      (node (ref "P7") (pin "3") (pinfunction "3_3") (pintype "passive"))
      (node (ref "P7") (pin "4") (pinfunction "4_4") (pintype "passive"))
      (node (ref "U31") (pin "8") (pinfunction "OUT(I)_8") (pintype "output"))
    )
    (net (code "155") (name "Net-(U31-OUT(M))") (class "Default")
      (node (ref "C87") (pin "-") (pinfunction "-_-") (pintype "passive"))
      (node (ref "C91") (pin "2") (pinfunction "2_2") (pintype "passive"))
      (node (ref "C92") (pin "1") (pinfunction "1_1") (pintype "passive"))
      (node (ref "P7") (pin "1") (pinfunction "1_1") (pintype "passive"))
      (node (ref "P7") (pin "2") (pinfunction "2_2") (pintype "passive"))
      (node (ref "U31") (pin "10") (pinfunction "OUT(M)_10") (pintype "passive"))
    )
    (net (code "156") (name "Net-(U32A-+IN)") (class "Default")
      (node (ref "C46") (pin "+") (pinfunction "+_+") (pintype "passive"))
      (node (ref "R33") (pin "2") (pinfunction "2_2") (pintype "passive"))
      (node (ref "R48") (pin "1") (pinfunction "1_1") (pintype "passive"))
      (node (ref "U32") (pin "3") (pinfunction "+IN_3") (pintype "input"))
    )
    (net (code "157") (name "Net-(U32A--IN)") (class "Default")
      (node (ref "R39") (pin "2") (pinfunction "2_2") (pintype "passive"))
      (node (ref "U32") (pin "1") (pinfunction "OUT_1") (pintype "output"))
      (node (ref "U32") (pin "2") (pinfunction "-IN_2") (pintype "input"))
    )
    (net (code "158") (name "Net-(U32B-+IN)") (class "Default")
      (node (ref "C48") (pin "1") (pinfunction "1_1") (pintype "passive"))
      (node (ref "R36") (pin "1") (pinfunction "1_1") (pintype "passive"))
      (node (ref "U32") (pin "5") (pinfunction "+IN_5") (pintype "input"))
    )
    (net (code "159") (name "Net-(U32C--IN)") (class "Default")
      (node (ref "C59") (pin "2") (pinfunction "2_2") (pintype "passive"))
      (node (ref "R46") (pin "1") (pinfunction "1_1") (pintype "passive"))
      (node (ref "U32") (pin "9") (pinfunction "-IN_9") (pintype "input"))
    )
    (net (code "160") (name "Net-(U32C-OUT)") (class "Default")
      (node (ref "C59") (pin "1") (pinfunction "1_1") (pintype "passive"))
      (node (ref "R45") (pin "1") (pinfunction "1_1") (pintype "passive"))
      (node (ref "R78") (pin "2") (pinfunction "2_2") (pintype "passive"))
      (node (ref "U32") (pin "8") (pinfunction "OUT_8") (pintype "output"))
    )
    (net (code "161") (name "Net-(U32D-+IN)") (class "Default")
      (node (ref "C50") (pin "1") (pinfunction "1_1") (pintype "passive"))
      (node (ref "R38") (pin "1") (pinfunction "1_1") (pintype "passive"))
      (node (ref "U32") (pin "12") (pinfunction "+IN_12") (pintype "input"))
    )
    (net (code "162") (name "Net-(U32D--IN)") (class "Default")
      (node (ref "C52") (pin "1") (pinfunction "1_1") (pintype "passive"))
      (node (ref "R35") (pin "2") (pinfunction "2_2") (pintype "passive"))
      (node (ref "U32") (pin "13") (pinfunction "-IN_13") (pintype "input"))
      (node (ref "U32") (pin "14") (pinfunction "OUT_14") (pintype "output"))
    )
    (net (code "163") (name "Net-(U33A--IN)") (class "Default")
      (node (ref "C71") (pin "2") (pinfunction "2_2") (pintype "passive"))
      (node (ref "R64") (pin "1") (pinfunction "1_1") (pintype "passive"))
      (node (ref "U33") (pin "2") (pinfunction "-IN_2") (pintype "input"))
    )
    (net (code "164") (name "Net-(U33A-OUT)") (class "Default")
      (node (ref "C71") (pin "1") (pinfunction "1_1") (pintype "passive"))
      (node (ref "R63") (pin "1") (pinfunction "1_1") (pintype "passive"))
      (node (ref "R79") (pin "2") (pinfunction "2_2") (pintype "passive"))
      (node (ref "U33") (pin "1") (pinfunction "OUT_1") (pintype "output"))
    )
    (net (code "165") (name "Net-(U33B--IN)") (class "Default")
      (node (ref "C60") (pin "2") (pinfunction "2_2") (pintype "passive"))
      (node (ref "R52") (pin "1") (pinfunction "1_1") (pintype "passive"))
      (node (ref "U33") (pin "6") (pinfunction "-IN_6") (pintype "input"))
    )
    (net (code "166") (name "Net-(U33B-OUT)") (class "Default")
      (node (ref "C60") (pin "1") (pinfunction "1_1") (pintype "passive"))
      (node (ref "R51") (pin "1") (pinfunction "1_1") (pintype "passive"))
      (node (ref "R77") (pin "2") (pinfunction "2_2") (pintype "passive"))
      (node (ref "U33") (pin "7") (pinfunction "OUT_7") (pintype "output"))
    )
    (net (code "167") (name "Net-(U33C--IN)") (class "Default")
      (node (ref "R67") (pin "2") (pinfunction "2_2") (pintype "passive"))
      (node (ref "R80") (pin "1") (pinfunction "1_1") (pintype "passive"))
      (node (ref "U33") (pin "9") (pinfunction "-IN_9") (pintype "input"))
    )
    (net (code "168") (name "Net-(U33C-OUT)") (class "Default")
      (node (ref "C75") (pin "+") (pinfunction "+_+") (pintype "passive"))
      (node (ref "R67") (pin "1") (pinfunction "1_1") (pintype "passive"))
      (node (ref "U33") (pin "8") (pinfunction "OUT_8") (pintype "output"))
    )
    (net (code "169") (name "Net-(U33D--IN)") (class "Default")
      (node (ref "C96") (pin "1") (pinfunction "1_1") (pintype "passive"))
      (node (ref "R53") (pin "1") (pinfunction "1_1") (pintype "passive"))
      (node (ref "R77") (pin "1") (pinfunction "1_1") (pintype "passive"))
      (node (ref "R78") (pin "1") (pinfunction "1_1") (pintype "passive"))
      (node (ref "R79") (pin "1") (pinfunction "1_1") (pintype "passive"))
      (node (ref "R81") (pin "1") (pinfunction "1_1") (pintype "passive"))
      (node (ref "R88") (pin "2") (pinfunction "2_2") (pintype "passive"))
      (node (ref "U33") (pin "13") (pinfunction "-IN_13") (pintype "input"))
    )
    (net (code "170") (name "Net-(U33D-OUT)") (class "Default")
      (node (ref "C68") (pin "+") (pinfunction "+_+") (pintype "passive"))
      (node (ref "C96") (pin "2") (pinfunction "2_2") (pintype "passive"))
      (node (ref "R88") (pin "1") (pinfunction "1_1") (pintype "passive"))
      (node (ref "U33") (pin "14") (pinfunction "OUT_14") (pintype "output"))
    )
    (net (code "171") (name "PCM-A0") (class "Default")
      (node (ref "U1") (pin "18") (pinfunction "A0_18") (pintype "passive"))
      (node (ref "U12") (pin "12") (pinfunction "A0_12") (pintype "passive"))
      (node (ref "U13") (pin "12") (pinfunction "A0_12") (pintype "passive"))
    )
    (net (code "172") (name "PCM-A1") (class "Default")
      (node (ref "U1") (pin "19") (pinfunction "A1_19") (pintype "passive"))
      (node (ref "U12") (pin "11") (pinfunction "A1_11") (pintype "passive"))
      (node (ref "U13") (pin "11") (pinfunction "A1_11") (pintype "passive"))
    )
    (net (code "173") (name "PCM-A2") (class "Default")
      (node (ref "U1") (pin "20") (pinfunction "A2_20") (pintype "passive"))
      (node (ref "U12") (pin "10") (pinfunction "A2_10") (pintype "passive"))
      (node (ref "U13") (pin "10") (pinfunction "A2_10") (pintype "passive"))
    )
    (net (code "174") (name "PCM-A3") (class "Default")
      (node (ref "U1") (pin "21") (pinfunction "A3_21") (pintype "passive"))
      (node (ref "U12") (pin "9") (pinfunction "A3_9") (pintype "passive"))
      (node (ref "U13") (pin "9") (pinfunction "A3_9") (pintype "passive"))
    )
    (net (code "175") (name "PCM-A4") (class "Default")
      (node (ref "U1") (pin "22") (pinfunction "A4_22") (pintype "passive"))
      (node (ref "U12") (pin "8") (pinfunction "A4_8") (pintype "passive"))
      (node (ref "U13") (pin "8") (pinfunction "A4_8") (pintype "passive"))
    )
    (net (code "176") (name "PCM-A5") (class "Default")
      (node (ref "U1") (pin "23") (pinfunction "A5_23") (pintype "passive"))
      (node (ref "U12") (pin "7") (pinfunction "A5_7") (pintype "passive"))
      (node (ref "U13") (pin "7") (pinfunction "A5_7") (pintype "passive"))
    )
    (net (code "177") (name "PCM-A6") (class "Default")
      (node (ref "U1") (pin "24") (pinfunction "A6_24") (pintype "passive"))
      (node (ref "U12") (pin "6") (pinfunction "A6_6") (pintype "passive"))
      (node (ref "U13") (pin "6") (pinfunction "A6_6") (pintype "passive"))
    )
    (net (code "178") (name "PCM-A7") (class "Default")
      (node (ref "U1") (pin "25") (pinfunction "A7_25") (pintype "passive"))
      (node (ref "U12") (pin "5") (pinfunction "A7_5") (pintype "passive"))
      (node (ref "U13") (pin "5") (pinfunction "A7_5") (pintype "passive"))
    )
    (net (code "179") (name "PCM-A8") (class "Default")
      (node (ref "U1") (pin "26") (pinfunction "A8_26") (pintype "passive"))
      (node (ref "U12") (pin "27") (pinfunction "A8_27") (pintype "passive"))
      (node (ref "U13") (pin "27") (pinfunction "A8_27") (pintype "passive"))
    )
    (net (code "180") (name "PCM-A9") (class "Default")
      (node (ref "U1") (pin "27") (pinfunction "A9_27") (pintype "passive"))
      (node (ref "U12") (pin "26") (pinfunction "A9_26") (pintype "passive"))
      (node (ref "U13") (pin "26") (pinfunction "A9_26") (pintype "passive"))
    )
    (net (code "181") (name "PCM-A10") (class "Default")
      (node (ref "U1") (pin "28") (pinfunction "A10_28") (pintype "passive"))
      (node (ref "U12") (pin "23") (pinfunction "A10_23") (pintype "passive"))
      (node (ref "U13") (pin "23") (pinfunction "A10_23") (pintype "passive"))
    )
    (net (code "182") (name "PCM-A11") (class "Default")
      (node (ref "U1") (pin "29") (pinfunction "A11_29") (pintype "passive"))
      (node (ref "U12") (pin "25") (pinfunction "A11_25") (pintype "passive"))
      (node (ref "U13") (pin "25") (pinfunction "A11_25") (pintype "passive"))
    )
    (net (code "183") (name "PCM-A12") (class "Default")
      (node (ref "U1") (pin "30") (pinfunction "A12_30") (pintype "passive"))
      (node (ref "U12") (pin "4") (pinfunction "A12_4") (pintype "passive"))
      (node (ref "U13") (pin "4") (pinfunction "A12_4") (pintype "passive"))
    )
    (net (code "184") (name "PCM-A13") (class "Default")
      (node (ref "U1") (pin "31") (pinfunction "A13_31") (pintype "passive"))
      (node (ref "U12") (pin "28") (pinfunction "A13_28") (pintype "passive"))
      (node (ref "U13") (pin "28") (pinfunction "A13_28") (pintype "passive"))
    )
    (net (code "185") (name "PCM-A14") (class "Default")
      (node (ref "U1") (pin "32") (pinfunction "A14_32") (pintype "passive"))
      (node (ref "U12") (pin "29") (pinfunction "A14_29") (pintype "passive"))
      (node (ref "U13") (pin "29") (pinfunction "A14_29") (pintype "passive"))
    )
    (net (code "186") (name "PCM-A15") (class "Default")
      (node (ref "U1") (pin "33") (pinfunction "A15_33") (pintype "passive"))
      (node (ref "U12") (pin "3") (pinfunction "A15_3") (pintype "passive"))
      (node (ref "U13") (pin "3") (pinfunction "A15_3") (pintype "passive"))
    )
    (net (code "187") (name "PCM-A16") (class "Default")
      (node (ref "U1") (pin "34") (pinfunction "A16_34") (pintype "passive"))
      (node (ref "U12") (pin "2") (pinfunction "A16_2") (pintype "passive"))
      (node (ref "U13") (pin "2") (pinfunction "A16_2") (pintype "passive"))
    )
    (net (code "188") (name "PCM-A17") (class "Default")
      (node (ref "U1") (pin "35") (pinfunction "A17_35") (pintype "passive"))
      (node (ref "U18") (pin "4") (pinfunction "4-IN_4") (pintype "passive"))
      (node (ref "U26") (pin "13") (pinfunction "I_13") (pintype "input"))
    )
    (net (code "189") (name "PCM-BS") (class "Default")
      (node (ref "U17") (pin "9") (pinfunction "CLK_9") (pintype "input"))
      (node (ref "U8") (pin "10") (pinfunction "Y5_10") (pintype "output"))
    )
    (net (code "190") (name "PCM-D0") (class "Default")
      (node (ref "U1") (pin "9") (pinfunction "SD0_9") (pintype "passive"))
      (node (ref "U12") (pin "13") (pinfunction "D0_13") (pintype "passive"))
      (node (ref "U13") (pin "13") (pinfunction "D0_13") (pintype "passive"))
    )
    (net (code "191") (name "PCM-D1") (class "Default")
      (node (ref "U1") (pin "10") (pinfunction "SD1_10") (pintype "passive"))
      (node (ref "U12") (pin "14") (pinfunction "D1_14") (pintype "passive"))
      (node (ref "U13") (pin "14") (pinfunction "D1_14") (pintype "passive"))
    )
    (net (code "192") (name "PCM-D2") (class "Default")
      (node (ref "U1") (pin "11") (pinfunction "SD2_11") (pintype "passive"))
      (node (ref "U12") (pin "15") (pinfunction "D2_15") (pintype "passive"))
      (node (ref "U13") (pin "15") (pinfunction "D2_15") (pintype "passive"))
    )
    (net (code "193") (name "PCM-D3") (class "Default")
      (node (ref "U1") (pin "12") (pinfunction "SD3_12") (pintype "passive"))
      (node (ref "U12") (pin "17") (pinfunction "D3_17") (pintype "passive"))
      (node (ref "U13") (pin "17") (pinfunction "D3_17") (pintype "passive"))
      (node (ref "U13") (pin "18") (pinfunction "D4_18") (pintype "passive"))
    )
    (net (code "194") (name "PCM-D4") (class "Default")
      (node (ref "U1") (pin "13") (pinfunction "SD4_13") (pintype "passive"))
      (node (ref "U12") (pin "18") (pinfunction "D4_18") (pintype "passive"))
    )
    (net (code "195") (name "PCM-D5") (class "Default")
      (node (ref "U1") (pin "14") (pinfunction "SD5_14") (pintype "passive"))
      (node (ref "U12") (pin "19") (pinfunction "D5_19") (pintype "passive"))
      (node (ref "U13") (pin "19") (pinfunction "D5_19") (pintype "passive"))
    )
    (net (code "196") (name "PCM-D6") (class "Default")
      (node (ref "U1") (pin "15") (pinfunction "SD6_15") (pintype "passive"))
      (node (ref "U12") (pin "20") (pinfunction "D6_20") (pintype "passive"))
      (node (ref "U13") (pin "20") (pinfunction "D6_20") (pintype "passive"))
    )
    (net (code "197") (name "PCM-D7") (class "Default")
      (node (ref "U1") (pin "16") (pinfunction "SD7_16") (pintype "passive"))
      (node (ref "U12") (pin "21") (pinfunction "D7_21") (pintype "passive"))
      (node (ref "U13") (pin "21") (pinfunction "D7_21") (pintype "passive"))
    )
    (net (code "198") (name "PCM-OUT") (class "Default")
      (node (ref "C58") (pin "1") (pinfunction "1_1") (pintype "passive"))
      (node (ref "R81") (pin "2") (pinfunction "2_2") (pintype "passive"))
      (node (ref "U32") (pin "6") (pinfunction "-IN_6") (pintype "input"))
      (node (ref "U32") (pin "7") (pinfunction "OUT_7") (pintype "output"))
    )
    (net (code "199") (name "RA17-0") (class "Default")
      (node (ref "U12") (pin "30") (pinfunction "A17_30") (pintype "passive"))
      (node (ref "U18") (pin "17") (pinfunction "I/O-17_17") (pintype "passive"))
    )
    (net (code "200") (name "RA17-1") (class "Default")
      (node (ref "U13") (pin "30") (pinfunction "A17_30") (pintype "passive"))
      (node (ref "U18") (pin "14") (pinfunction "I/O-14_14") (pintype "passive"))
    )
    (net (code "201") (name "RA18-0") (class "Default")
      (node (ref "U12") (pin "31") (pinfunction "A18_31") (pintype "passive"))
      (node (ref "U18") (pin "12") (pinfunction "OUT-12_12") (pintype "passive"))
    )
    (net (code "202") (name "RA18-1") (class "Default")
      (node (ref "U13") (pin "31") (pinfunction "A18_31") (pintype "passive"))
      (node (ref "U18") (pin "13") (pinfunction "I/O-13_13") (pintype "passive"))
    )
    (net (code "203") (name "RD-LATCH") (class "Default")
      (node (ref "U10") (pin "12") (pinfunction "~{EN}_12") (pintype "bidirectional"))
      (node (ref "U23") (pin "10") (pinfunction "PRE_10") (pintype "input"))
      (node (ref "U24") (pin "7") (pinfunction "INB_7") (pintype "input"))
      (node (ref "U6") (pin "12") (pinfunction "~{EN}_12") (pintype "bidirectional"))
      (node (ref "U8") (pin "11") (pinfunction "Y4_11") (pintype "output"))
    )
    (net (code "204") (name "RESET") (class "Default")
      (node (ref "R3") (pin "1") (pinfunction "1_1") (pintype "passive"))
      (node (ref "U1") (pin "8") (pinfunction "~{RESET}_8") (pintype "passive"))
      (node (ref "U14") (pin "3") (pinfunction "~{RESET}_3") (pintype "passive"))
      (node (ref "U19") (pin "12") (pinfunction "O_12") (pintype "output"))
      (node (ref "U28") (pin "7") (pinfunction "~{RESET}_7") (pintype "passive"))
      (node (ref "U4") (pin "37") (pinfunction "~{RESET}_37") (pintype "passive"))
    )
    (net (code "205") (name "R{slash}W") (class "Default")
      (node (ref "U18") (pin "9") (pinfunction "9-IN_9") (pintype "passive"))
      (node (ref "U4") (pin "32") (pinfunction "R/W_32") (pintype "passive"))
    )
    (net (code "206") (name "SNDVIDRD") (class "Default")
      (node (ref "C105") (pin "2") (pinfunction "2_2") (pintype "passive"))
      (node (ref "R86") (pin "1") (pinfunction "1_1") (pintype "passive"))
      (node (ref "R95") (pin "1") (pinfunction "1_1") (pintype "passive"))
      (node (ref "U25") (pin "10") (pinfunction "INC_10") (pintype "bidirectional"))
    )
    (net (code "207") (name "SND_DAT0") (class "Default")
      (node (ref "C35") (pin "1") (pinfunction "1_1") (pintype "passive"))
      (node (ref "P1") (pin "3") (pinfunction "3_3") (pintype "passive"))
      (node (ref "R11") (pin "2") (pinfunction "2_2") (pintype "passive"))
    )
    (net (code "208") (name "SND_DAT1") (class "Default")
      (node (ref "C37") (pin "1") (pinfunction "1_1") (pintype "passive"))
      (node (ref "P1") (pin "4") (pinfunction "4_4") (pintype "passive"))
      (node (ref "R13") (pin "2") (pinfunction "2_2") (pintype "passive"))
    )
    (net (code "209") (name "SND_DAT2") (class "Default")
      (node (ref "C38") (pin "1") (pinfunction "1_1") (pintype "passive"))
      (node (ref "P1") (pin "5") (pinfunction "5_5") (pintype "passive"))
      (node (ref "R14") (pin "2") (pinfunction "2_2") (pintype "passive"))
    )
    (net (code "210") (name "SND_DAT3") (class "Default")
      (node (ref "C36") (pin "1") (pinfunction "1_1") (pintype "passive"))
      (node (ref "P1") (pin "6") (pinfunction "6_6") (pintype "passive"))
      (node (ref "R12") (pin "2") (pinfunction "2_2") (pintype "passive"))
    )
    (net (code "211") (name "SND_DAT4") (class "Default")
      (node (ref "C39") (pin "1") (pinfunction "1_1") (pintype "passive"))
      (node (ref "P1") (pin "7") (pinfunction "7_7") (pintype "passive"))
      (node (ref "R15") (pin "2") (pinfunction "2_2") (pintype "passive"))
    )
    (net (code "212") (name "SND_DAT5") (class "Default")
      (node (ref "C40") (pin "1") (pinfunction "1_1") (pintype "passive"))
      (node (ref "P1") (pin "8") (pinfunction "8_8") (pintype "passive"))
      (node (ref "R16") (pin "2") (pinfunction "2_2") (pintype "passive"))
    )
    (net (code "213") (name "SND_DAT6") (class "Default")
      (node (ref "C41") (pin "1") (pinfunction "1_1") (pintype "passive"))
      (node (ref "P1") (pin "9") (pinfunction "9_9") (pintype "passive"))
      (node (ref "R17") (pin "2") (pinfunction "2_2") (pintype "passive"))
    )
    (net (code "214") (name "SND_DAT7") (class "Default")
      (node (ref "C42") (pin "1") (pinfunction "1_1") (pintype "passive"))
      (node (ref "P1") (pin "10") (pinfunction "10_10") (pintype "passive"))
      (node (ref "R18") (pin "2") (pinfunction "2_2") (pintype "passive"))
    )
    (net (code "215") (name "SND_DAT8") (class "Default")
      (node (ref "C107") (pin "1") (pinfunction "1_1") (pintype "passive"))
      (node (ref "R84") (pin "1") (pinfunction "1_1") (pintype "passive"))
      (node (ref "R94") (pin "1") (pinfunction "1_1") (pintype "passive"))
      (node (ref "U25") (pin "2") (pinfunction "INA_2") (pintype "bidirectional"))
    )
    (net (code "216") (name "SND_DAV") (class "Default")
      (node (ref "C45") (pin "1") (pinfunction "1_1") (pintype "passive"))
      (node (ref "P1") (pin "19") (pinfunction "19_19") (pintype "passive"))
      (node (ref "R21") (pin "2") (pinfunction "2_2") (pintype "passive"))
    )
    (net (code "217") (name "SND_RDY") (class "Default")
      (node (ref "C43") (pin "1") (pinfunction "1_1") (pintype "passive"))
      (node (ref "P1") (pin "11") (pinfunction "11_11") (pintype "passive"))
      (node (ref "R19") (pin "2") (pinfunction "2_2") (pintype "passive"))
    )
    (net (code "218") (name "SOFT_RES") (class "Default")
      (node (ref "U19") (pin "13") (pinfunction "I2_13") (pintype "input"))
      (node (ref "U25") (pin "3") (pinfunction "OUTA_3") (pintype "bidirectional"))
    )
    (net (code "219") (name "VIDPWRON") (class "Default")
      (node (ref "U19") (pin "2") (pinfunction "I1_2") (pintype "input"))
      (node (ref "U25") (pin "5") (pinfunction "OUTB_5") (pintype "bidirectional"))
    )
    (net (code "220") (name "VIDSNDRD") (class "Default")
      (node (ref "U11") (pin "12") (pinfunction "~{EN}_12") (pintype "bidirectional"))
      (node (ref "U25") (pin "11") (pinfunction "OUTC_11") (pintype "bidirectional"))
      (node (ref "U7") (pin "12") (pinfunction "~{EN}_12") (pintype "bidirectional"))
      (node (ref "U9") (pin "13") (pinfunction "CLR_13") (pintype "input"))
    )
    (net (code "221") (name "WR-LATCH") (class "Default")
      (node (ref "U5") (pin "11") (pinfunction "CLK_11") (pintype "input"))
      (node (ref "U8") (pin "7") (pinfunction "Y7_7") (pintype "output"))
      (node (ref "U9") (pin "11") (pinfunction "CLK_11") (pintype "input"))
    )
    (net (code "222") (name "YAM") (class "Default")
      (node (ref "U14") (pin "7") (pinfunction "~{CS}_7") (pintype "passive"))
      (node (ref "U8") (pin "14") (pinfunction "Y1_14") (pintype "output"))
    )
    (net (code "223") (name "YAM1-OUT") (class "Default")
      (node (ref "C53") (pin "+") (pinfunction "+_+") (pintype "passive"))
      (node (ref "R40") (pin "2") (pinfunction "2_2") (pintype "passive"))
    )
    (net (code "224") (name "YAM2-OUT") (class "Default")
      (node (ref "C57") (pin "+") (pinfunction "+_+") (pintype "passive"))
      (node (ref "R44") (pin "2") (pinfunction "2_2") (pintype "passive"))
    )
    (net (code "225") (name "unconnected-(P1-Pad2)") (class "Default")
      (node (ref "P1") (pin "2") (pinfunction "2_2") (pintype "passive"))
    )
    (net (code "226") (name "unconnected-(P1-Pad12)") (class "Default")
      (node (ref "P1") (pin "12") (pinfunction "12_12") (pintype "passive"))
    )
    (net (code "227") (name "unconnected-(P1-Pad14)") (class "Default")
      (node (ref "P1") (pin "14") (pinfunction "14_14") (pintype "passive"))
    )
    (net (code "228") (name "unconnected-(P1-Pad20)") (class "Default")
      (node (ref "P1") (pin "20") (pinfunction "20_20") (pintype "passive"))
    )
    (net (code "229") (name "unconnected-(P2-Pad2)") (class "Default")
      (node (ref "P2") (pin "2") (pinfunction "2_2") (pintype "passive"))
    )
    (net (code "230") (name "unconnected-(P3-Pad2)") (class "Default")
      (node (ref "P3") (pin "2") (pinfunction "2_2") (pintype "passive"))
    )
    (net (code "231") (name "unconnected-(P4-Pad2)") (class "Default")
      (node (ref "P4") (pin "2") (pinfunction "2_2") (pintype "passive"))
    )
    (net (code "232") (name "unconnected-(P4-Pad3)") (class "Default")
      (node (ref "P4") (pin "3") (pinfunction "3_3") (pintype "passive"))
    )
    (net (code "233") (name "unconnected-(P5-Pad1)") (class "Default")
      (node (ref "P5") (pin "1") (pinfunction "1_1") (pintype "passive"))
    )
    (net (code "234") (name "unconnected-(P5-Pad3)") (class "Default")
      (node (ref "P5") (pin "3") (pinfunction "3_3") (pintype "passive"))
    )
    (net (code "235") (name "unconnected-(P6-Pad3)") (class "Default")
      (node (ref "P6") (pin "3") (pinfunction "3_3") (pintype "passive"))
    )
    (net (code "236") (name "unconnected-(P6-Pad4)") (class "Default")
      (node (ref "P6") (pin "4") (pinfunction "4_4") (pintype "passive"))
    )
    (net (code "237") (name "unconnected-(U1-~{XTAL}-Pad6)") (class "Default")
      (node (ref "U1") (pin "6") (pinfunction "~{XTAL}_6") (pintype "passive"))
    )
    (net (code "238") (name "unconnected-(U4-AVMA-Pad36)") (class "Default")
      (node (ref "U4") (pin "36") (pinfunction "AVMA_36") (pintype "passive"))
    )
    (net (code "239") (name "unconnected-(U4-BA-Pad6)") (class "Default")
      (node (ref "U4") (pin "6") (pinfunction "BA_6") (pintype "passive"))
    )
    (net (code "240") (name "unconnected-(U4-BS-Pad5)") (class "Default")
      (node (ref "U4") (pin "5") (pinfunction "BS_5") (pintype "passive"))
    )
    (net (code "241") (name "unconnected-(U4-BUSY-Pad33)") (class "Default")
      (node (ref "U4") (pin "33") (pinfunction "BUSY_33") (pintype "passive"))
    )
    (net (code "242") (name "unconnected-(U4-LIC-Pad38)") (class "Default")
      (node (ref "U4") (pin "38") (pinfunction "LIC_38") (pintype "passive"))
    )
    (net (code "243") (name "unconnected-(U4-VCC-Pad7)") (class "Default")
      (node (ref "U4") (pin "7") (pinfunction "VCC_7") (pintype "passive"))
    )
    (net (code "244") (name "unconnected-(U7-~{OUTA}-Pad3)") (class "Default")
      (node (ref "U7") (pin "3") (pinfunction "~{OUTA}_3") (pintype "bidirectional"))
    )
    (net (code "245") (name "unconnected-(U7-~{OUTB}-Pad5)") (class "Default")
      (node (ref "U7") (pin "5") (pinfunction "~{OUTB}_5") (pintype "bidirectional"))
    )
    (net (code "246") (name "unconnected-(U7-~{OUTC}-Pad11)") (class "Default")
      (node (ref "U7") (pin "11") (pinfunction "~{OUTC}_11") (pintype "bidirectional"))
    )
    (net (code "247") (name "unconnected-(U7-~{OUTD}-Pad13)") (class "Default")
      (node (ref "U7") (pin "13") (pinfunction "~{OUTD}_13") (pintype "bidirectional"))
    )
    (net (code "248") (name "unconnected-(U8A-Y6-Pad9)") (class "Default")
      (node (ref "U8") (pin "9") (pinfunction "Y6_9") (pintype "output"))
    )
    (net (code "249") (name "unconnected-(U9B-~{Q}-Pad8)") (class "Default")
      (node (ref "U9") (pin "8") (pinfunction "~{Q}_8") (pintype "output"))
    )
    (net (code "250") (name "unconnected-(U11-~{OUTA}-Pad3)") (class "Default")
      (node (ref "U11") (pin "3") (pinfunction "~{OUTA}_3") (pintype "bidirectional"))
    )
    (net (code "251") (name "unconnected-(U11-~{OUTB}-Pad5)") (class "Default")
      (node (ref "U11") (pin "5") (pinfunction "~{OUTB}_5") (pintype "bidirectional"))
    )
    (net (code "252") (name "unconnected-(U11-~{OUTC}-Pad11)") (class "Default")
      (node (ref "U11") (pin "11") (pinfunction "~{OUTC}_11") (pintype "bidirectional"))
    )
    (net (code "253") (name "unconnected-(U11-~{OUTD}-Pad13)") (class "Default")
      (node (ref "U11") (pin "13") (pinfunction "~{OUTD}_13") (pintype "bidirectional"))
    )
    (net (code "254") (name "unconnected-(U14-CT1-Pad8)") (class "Default")
      (node (ref "U14") (pin "8") (pinfunction "CT1_8") (pintype "passive"))
    )
    (net (code "255") (name "unconnected-(U14-CT2-Pad9)") (class "Default")
      (node (ref "U14") (pin "9") (pinfunction "CT2_9") (pintype "passive"))
    )
    (net (code "256") (name "unconnected-(U15-RFB-Pad16)") (class "Default")
      (node (ref "U15") (pin "16") (pinfunction "RFB_16") (pintype "passive"))
    )
    (net (code "257") (name "unconnected-(U16A-5Q-Pad12)") (class "Default")
      (node (ref "U16") (pin "12") (pinfunction "5Q_12") (pintype "tri_state"))
    )
    (net (code "258") (name "unconnected-(U16A-6Q-Pad15)") (class "Default")
      (node (ref "U16") (pin "15") (pinfunction "6Q_15") (pintype "tri_state"))
    )
    (net (code "259") (name "unconnected-(U16A-7Q-Pad16)") (class "Default")
      (node (ref "U16") (pin "16") (pinfunction "7Q_16") (pintype "tri_state"))
    )
    (net (code "260") (name "unconnected-(U16A-8Q-Pad19)") (class "Default")
      (node (ref "U16") (pin "19") (pinfunction "8Q_19") (pintype "tri_state"))
    )
    (net (code "261") (name "unconnected-(U17A-Q1-Pad2)") (class "Default")
      (node (ref "U17") (pin "2") (pinfunction "Q1_2") (pintype "output"))
    )
    (net (code "262") (name "unconnected-(U17A-Q4-Pad10)") (class "Default")
      (node (ref "U17") (pin "10") (pinfunction "Q4_10") (pintype "output"))
    )
    (net (code "263") (name "unconnected-(U17A-Q5-Pad12)") (class "Default")
      (node (ref "U17") (pin "12") (pinfunction "Q5_12") (pintype "output"))
    )
    (net (code "264") (name "unconnected-(U20B-Y2-Pad10)") (class "Default")
      (node (ref "U20") (pin "10") (pinfunction "Y2_10") (pintype "output"))
    )
    (net (code "265") (name "unconnected-(U20B-Y3-Pad9)") (class "Default")
      (node (ref "U20") (pin "9") (pinfunction "Y3_9") (pintype "output"))
    )
    (net (code "266") (name "unconnected-(U21A-O-Pad12)") (class "Default")
      (node (ref "U21") (pin "12") (pinfunction "O_12") (pintype "output"))
    )
    (net (code "267") (name "unconnected-(U21B-O-Pad10)") (class "Default")
      (node (ref "U21") (pin "10") (pinfunction "O_10") (pintype "output"))
    )
    (net (code "268") (name "unconnected-(U21E-O-Pad4)") (class "Default")
      (node (ref "U21") (pin "4") (pinfunction "O_4") (pintype "output"))
    )
    (net (code "269") (name "unconnected-(U22B-Q-Pad9)") (class "Default")
      (node (ref "U22") (pin "9") (pinfunction "Q_9") (pintype "output"))
    )
    (net (code "270") (name "unconnected-(U22B-~{Q}-Pad8)") (class "Default")
      (node (ref "U22") (pin "8") (pinfunction "~{Q}_8") (pintype "output"))
    )
    (net (code "271") (name "unconnected-(U23B-~{Q}-Pad8)") (class "Default")
      (node (ref "U23") (pin "8") (pinfunction "~{Q}_8") (pintype "output"))
    )
    (net (code "272") (name "unconnected-(U24-OUTC-Pad10)") (class "Default")
      (node (ref "U24") (pin "10") (pinfunction "OUTC_10") (pintype "bidirectional"))
    )
    (net (code "273") (name "unconnected-(U24-~{OUTA}-Pad3)") (class "Default")
      (node (ref "U24") (pin "3") (pinfunction "~{OUTA}_3") (pintype "bidirectional"))
    )
    (net (code "274") (name "unconnected-(U24-~{OUTB}-Pad5)") (class "Default")
      (node (ref "U24") (pin "5") (pinfunction "~{OUTB}_5") (pintype "bidirectional"))
    )
    (net (code "275") (name "unconnected-(U24-~{OUTC}-Pad11)") (class "Default")
      (node (ref "U24") (pin "11") (pinfunction "~{OUTC}_11") (pintype "bidirectional"))
    )
    (net (code "276") (name "unconnected-(U24-~{OUTD}-Pad13)") (class "Default")
      (node (ref "U24") (pin "13") (pinfunction "~{OUTD}_13") (pintype "bidirectional"))
    )
    (net (code "277") (name "unconnected-(U31-NC-Pad2)") (class "Default")
      (node (ref "U31") (pin "2") (pinfunction "NC_2") (pintype "no_connect"))
    )
    (net (code "278") (name "unconnected-(Y2-EN-Pad1)") (class "Default")
      (node (ref "Y2") (pin "1") (pinfunction "EN_1") (pintype "bidirectional"))
    )
    (net (code "279") (name "{slash}E") (class "Default")
      (node (ref "C62") (pin "1") (pinfunction "1_1") (pintype "passive"))
      (node (ref "R28") (pin "1") (pinfunction "1_1") (pintype "passive"))
      (node (ref "U18") (pin "5") (pinfunction "5-IN_5") (pintype "passive"))
      (node (ref "U22") (pin "6") (pinfunction "~{Q}_6") (pintype "output"))
      (node (ref "U23") (pin "2") (pinfunction "D_2") (pintype "input"))
    )
    (net (code "280") (name "{slash}EORQ") (class "Default")
      (node (ref "U18") (pin "15") (pinfunction "I/O-15_15") (pintype "passive"))
      (node (ref "U20") (pin "1") (pinfunction "G_1") (pintype "input"))
    )
    (net (code "281") (name "{slash}Q") (class "Default")
      (node (ref "U18") (pin "6") (pinfunction "6-IN_6") (pintype "passive"))
      (node (ref "U23") (pin "6") (pinfunction "~{Q}_6") (pintype "output"))
    )
    (net (code "282") (name "{slash}RAMWR") (class "Default")
      (node (ref "U18") (pin "16") (pinfunction "I/O-16_16") (pintype "passive"))
      (node (ref "W6") (pin "1") (pinfunction "1_1") (pintype "passive"))
    )
    (net (code "283") (name "{slash}RD") (class "Default")
      (node (ref "U1") (pin "2") (pinfunction "~{RD}_2") (pintype "passive"))
      (node (ref "U14") (pin "6") (pinfunction "~{RD}_6") (pintype "passive"))
      (node (ref "U18") (pin "18") (pinfunction "I/O-18_18") (pintype "passive"))
      (node (ref "U2") (pin "22") (pinfunction "~{OE}_22") (pintype "input"))
    )
    (net (code "284") (name "{slash}WR") (class "Default")
      (node (ref "U1") (pin "3") (pinfunction "~{WR}_3") (pintype "passive"))
      (node (ref "U14") (pin "5") (pinfunction "~{WR}_5") (pintype "passive"))
      (node (ref "U15") (pin "13") (pinfunction "~{WR}_13") (pintype "input"))
      (node (ref "U18") (pin "19") (pinfunction "OUT-19_19") (pintype "passive"))
      (node (ref "U2") (pin "27") (pinfunction "~{WE}_27") (pintype "input"))
    )
  )
)
